# AFPGA.net
KiCad netlist of a schematic drawn in Altium Designer
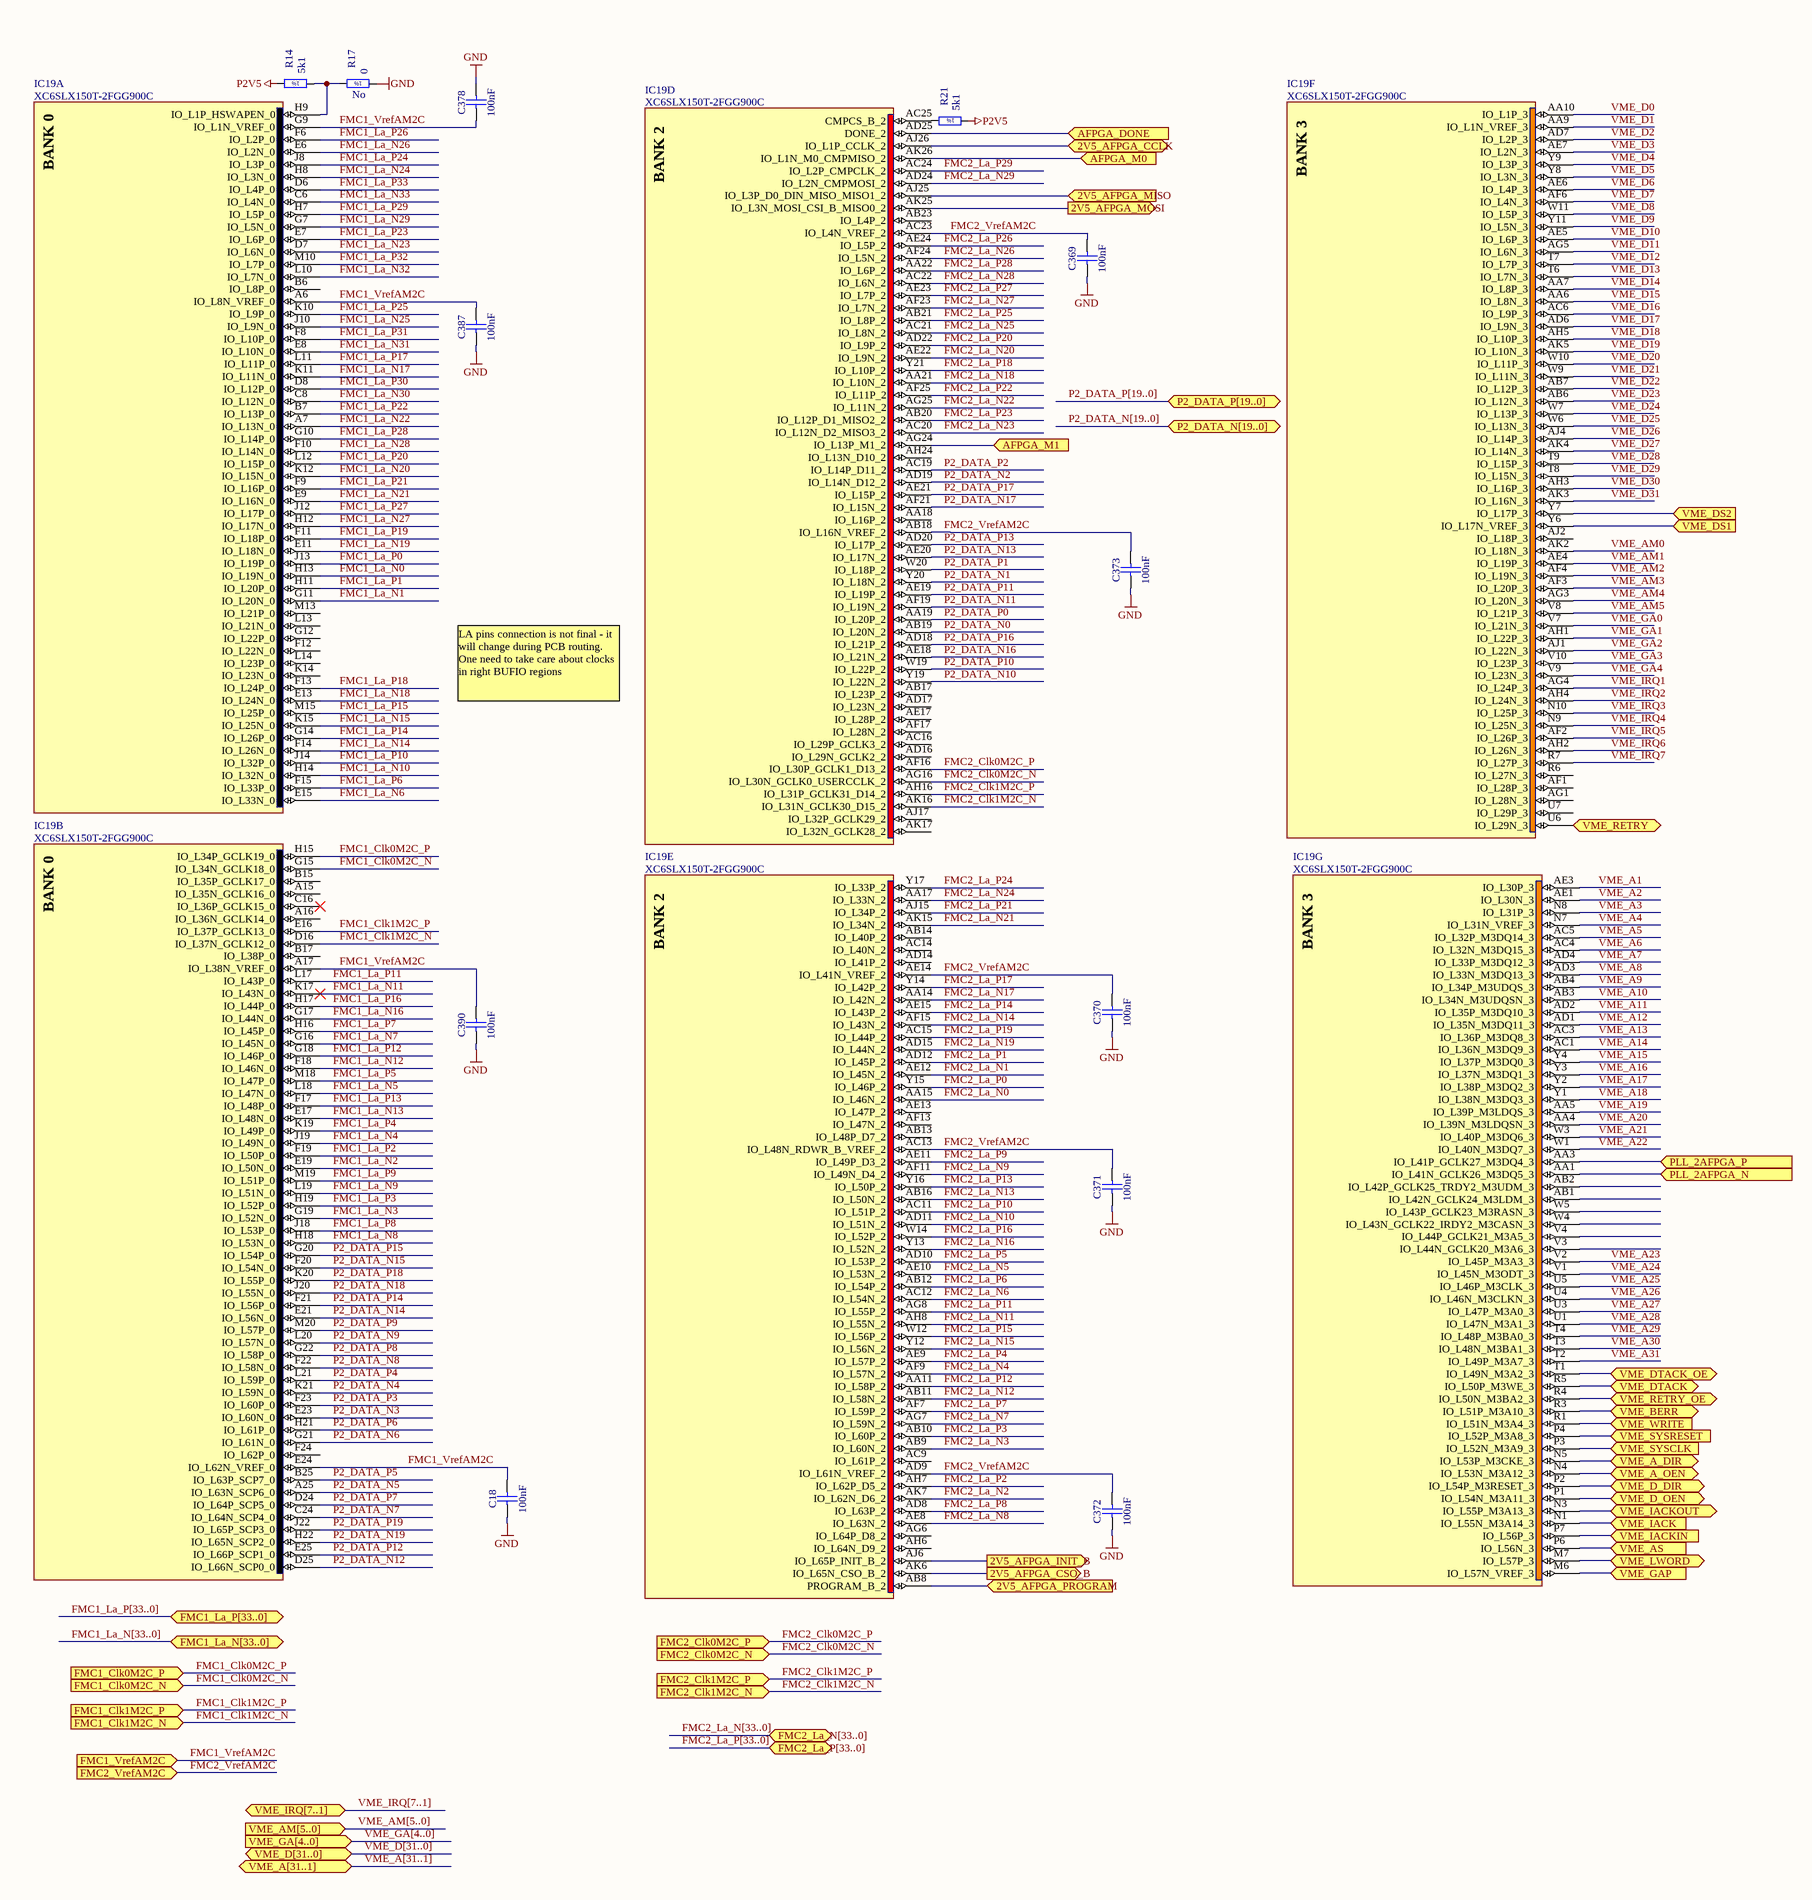
[diagram p0: AFPGA.SchDoc, left]
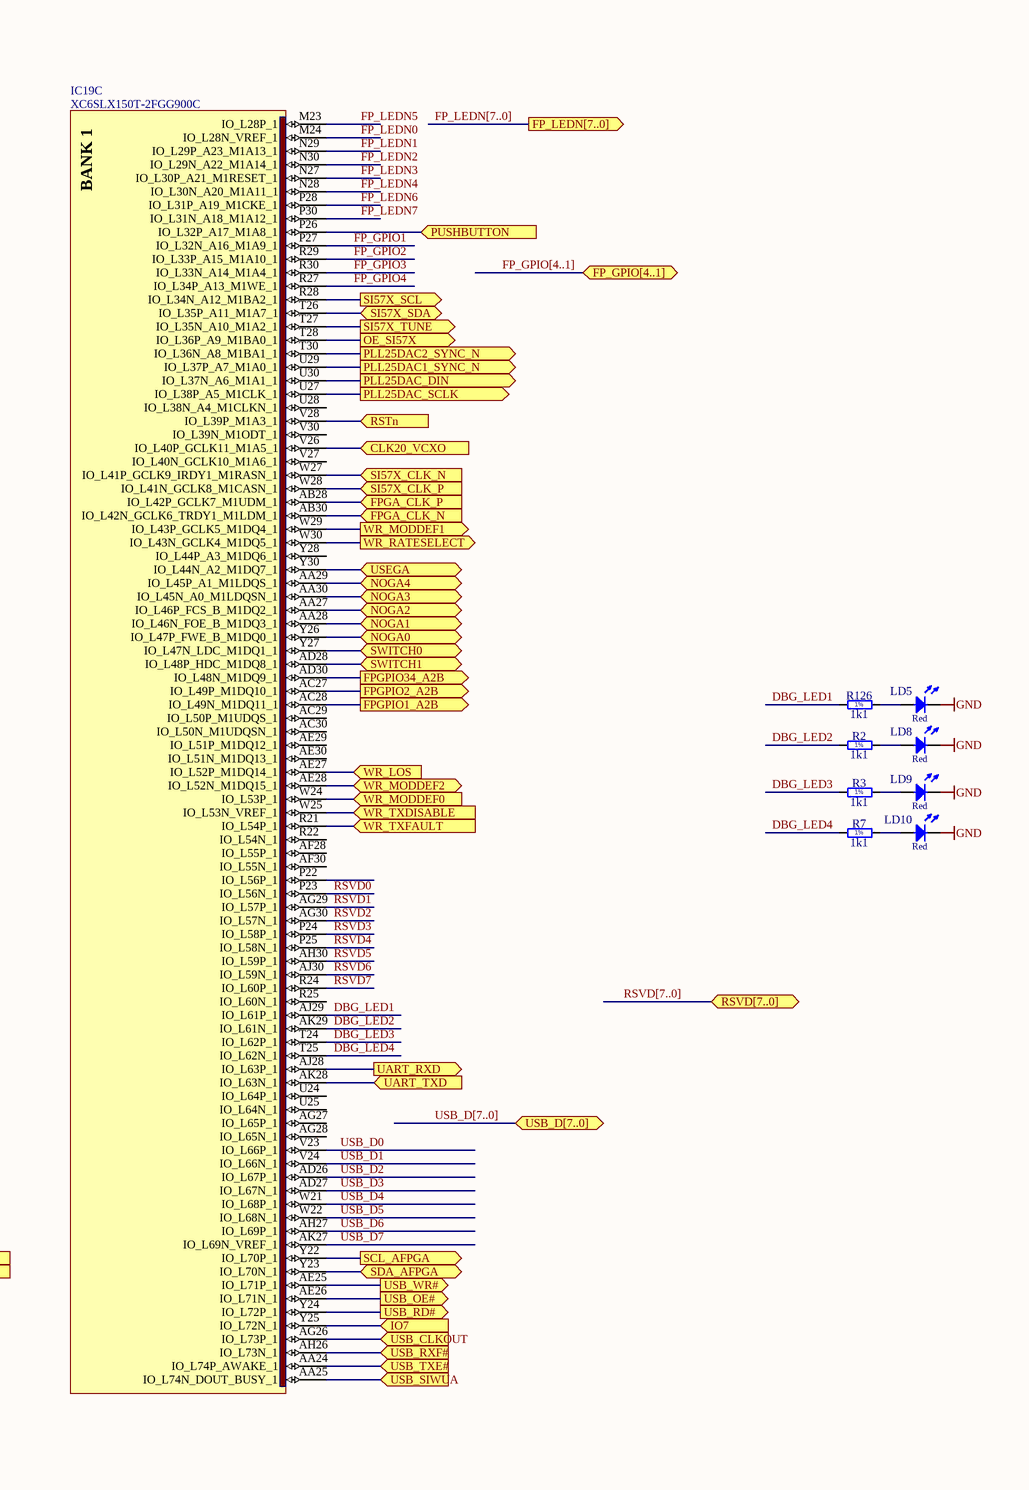
[diagram p1: AFPGA.SchDoc, right]

(export (version "E")
  (design (tool "Eeschema 10.0.6"))
  (components
    (comp (ref "C18")
      (value "100nF")
      (footprint "CAPC1005X55N")
      (description "Non-polarised capacitor")
      (fields
        (field (name "PART NUMBER") "CC0402_100NF_16V_10%_X7R")
        (field (name "VOLTAGE") "16V")
        (field (name "AUTHOR") "CERN DEM JLC")
      )
      (libsource (lib "Capacitors") (part "Capacitor - non polarized"))
    )
    (comp (ref "C369")
      (value "100nF")
      (footprint "CAPC1005X55N")
      (description "Non-polarised capacitor")
      (fields
        (field (name "PART NUMBER") "CC0402_100NF_16V_10%_X7R")
        (field (name "VOLTAGE") "16V")
        (field (name "AUTHOR") "CERN DEM JLC")
      )
      (libsource (lib "Capacitors") (part "Capacitor - non polarized"))
    )
    (comp (ref "C370")
      (value "100nF")
      (footprint "CAPC1005X55N")
      (description "Non-polarised capacitor")
      (fields
        (field (name "PART NUMBER") "CC0402_100NF_16V_10%_X7R")
        (field (name "VOLTAGE") "16V")
        (field (name "AUTHOR") "CERN DEM JLC")
      )
      (libsource (lib "Capacitors") (part "Capacitor - non polarized"))
    )
    (comp (ref "C371")
      (value "100nF")
      (footprint "CAPC1005X55N")
      (description "Non-polarised capacitor")
      (fields
        (field (name "PART NUMBER") "CC0402_100NF_16V_10%_X7R")
        (field (name "VOLTAGE") "16V")
        (field (name "AUTHOR") "CERN DEM JLC")
      )
      (libsource (lib "Capacitors") (part "Capacitor - non polarized"))
    )
    (comp (ref "C372")
      (value "100nF")
      (footprint "CAPC1005X55N")
      (description "Non-polarised capacitor")
      (fields
        (field (name "PART NUMBER") "CC0402_100NF_16V_10%_X7R")
        (field (name "VOLTAGE") "16V")
        (field (name "AUTHOR") "CERN DEM JLC")
      )
      (libsource (lib "Capacitors") (part "Capacitor - non polarized"))
    )
    (comp (ref "C373")
      (value "100nF")
      (footprint "CAPC1005X55N")
      (description "Non-polarised capacitor")
      (fields
        (field (name "PART NUMBER") "CC0402_100NF_16V_10%_X7R")
        (field (name "VOLTAGE") "16V")
        (field (name "AUTHOR") "CERN DEM JLC")
      )
      (libsource (lib "Capacitors") (part "Capacitor - non polarized"))
    )
    (comp (ref "C378")
      (value "100nF")
      (footprint "CAPC1005X55N")
      (description "Non-polarised capacitor")
      (fields
        (field (name "PART NUMBER") "CC0402_100NF_16V_10%_X7R")
        (field (name "VOLTAGE") "16V")
        (field (name "AUTHOR") "CERN DEM JLC")
      )
      (libsource (lib "Capacitors") (part "Capacitor - non polarized"))
    )
    (comp (ref "C387")
      (value "100nF")
      (footprint "CAPC1005X55N")
      (description "Non-polarised capacitor")
      (fields
        (field (name "PART NUMBER") "CC0402_100NF_16V_10%_X7R")
        (field (name "VOLTAGE") "16V")
        (field (name "AUTHOR") "CERN DEM JLC")
      )
      (libsource (lib "Capacitors") (part "Capacitor - non polarized"))
    )
    (comp (ref "C390")
      (value "100nF")
      (footprint "CAPC1005X55N")
      (description "Non-polarised capacitor")
      (fields
        (field (name "PART NUMBER") "CC0402_100NF_16V_10%_X7R")
        (field (name "VOLTAGE") "16V")
        (field (name "AUTHOR") "CERN DEM JLC")
      )
      (libsource (lib "Capacitors") (part "Capacitor - non polarized"))
    )
    (comp (ref "IC19")
      (value "XC6SLX150T-2FGG900C")
      (footprint "BGA900C100P30X30_3100X3100X260")
      (description "SPARTAN-6, FPGA, 900-Ball BGA, Commercial Grade, Pb-Free")
      (fields (field (name "MANUFACTURER") "XILINX") (field (name "AUTHOR") "CERN DEM JLC"))
      (libsource (lib "ICs And Semiconductors") (part "XC6SLX150T-2FGG900C"))
    )
    (comp (ref "LD5")
      (value "Red")
      (footprint "LEDC1608X80N_RED")
      (description "LED Red 1C 2A")
      (fields
        (field (name "PART NUMBER") "LED_ROHM_SML-311UTT86K")
        (field (name "MANUFACTURER") "ROHM")
        (field (name "AUTHOR") "CERN DEM JLC")
      )
      (libsource (lib "ICs And Semiconductors") (part "LED Red 1C 2A"))
    )
    (comp (ref "LD8")
      (value "Red")
      (footprint "LEDC1608X80N_RED")
      (description "LED Red 1C 2A")
      (fields
        (field (name "PART NUMBER") "LED_ROHM_SML-311UTT86K")
        (field (name "MANUFACTURER") "ROHM")
        (field (name "AUTHOR") "CERN DEM JLC")
      )
      (libsource (lib "ICs And Semiconductors") (part "LED Red 1C 2A"))
    )
    (comp (ref "LD9")
      (value "Red")
      (footprint "LEDC1608X80N_RED")
      (description "LED Red 1C 2A")
      (fields
        (field (name "PART NUMBER") "LED_ROHM_SML-311UTT86K")
        (field (name "MANUFACTURER") "ROHM")
        (field (name "AUTHOR") "CERN DEM JLC")
      )
      (libsource (lib "ICs And Semiconductors") (part "LED Red 1C 2A"))
    )
    (comp (ref "LD10")
      (value "Red")
      (footprint "LEDC1608X80N_RED")
      (description "LED Red 1C 2A")
      (fields
        (field (name "PART NUMBER") "LED_ROHM_SML-311UTT86K")
        (field (name "MANUFACTURER") "ROHM")
        (field (name "AUTHOR") "CERN DEM JLC")
      )
      (libsource (lib "ICs And Semiconductors") (part "LED Red 1C 2A"))
    )
    (comp (ref "R2")
      (value "1k1")
      (footprint "RESC1608X55N")
      (description "Resistor - 1%")
      (fields
        (field (name "PART NUMBER") "R0603_1K1_1%_0.1W_100PPM")
        (field (name "POWER") "0.1W")
        (field (name "AUTHOR") "CERN DEM JLC")
      )
      (libsource (lib "Resistors") (part "Resistor - 1%"))
    )
    (comp (ref "R3")
      (value "1k1")
      (footprint "RESC1608X55N")
      (description "Resistor - 1%")
      (fields
        (field (name "PART NUMBER") "R0603_1K1_1%_0.1W_100PPM")
        (field (name "POWER") "0.1W")
        (field (name "AUTHOR") "CERN DEM JLC")
      )
      (libsource (lib "Resistors") (part "Resistor - 1%"))
    )
    (comp (ref "R7")
      (value "1k1")
      (footprint "RESC1608X55N")
      (description "Resistor - 1%")
      (fields
        (field (name "PART NUMBER") "R0603_1K1_1%_0.1W_100PPM")
        (field (name "POWER") "0.1W")
        (field (name "AUTHOR") "CERN DEM JLC")
      )
      (libsource (lib "Resistors") (part "Resistor - 1%"))
    )
    (comp (ref "R14")
      (value "5k1")
      (footprint "RESC1608X55N")
      (description "Resistor - 1%")
      (fields
        (field (name "PART NUMBER") "R0603_5K1_1%_0.1W_100PPM")
        (field (name "POWER") "0.1W")
        (field (name "AUTHOR") "CERN DEM JLC")
      )
      (libsource (lib "Resistors") (part "Resistor - 1%"))
    )
    (comp (ref "R17")
      (value "0")
      (footprint "RESC1608X55N")
      (description "Resistor - 1%")
      (fields
        (field (name "PART NUMBER") "R0603_0R_JUMPER")
        (field (name "MANUFACTURER") "GENERIC")
        (field (name "MOUNTED") "No")
        (field (name "AUTHOR") "CERN DEM JLC")
      )
      (libsource (lib "Resistors") (part "Resistor - 1%"))
    )
    (comp (ref "R21")
      (value "5k1")
      (footprint "RESC1608X55N")
      (description "Resistor - 1%")
      (fields
        (field (name "PART NUMBER") "R0603_5K1_1%_0.1W_100PPM")
        (field (name "POWER") "0.1W")
        (field (name "AUTHOR") "CERN DEM JLC")
      )
      (libsource (lib "Resistors") (part "Resistor - 1%"))
    )
    (comp (ref "R126")
      (value "1k1")
      (footprint "RESC1608X55N")
      (description "Resistor - 1%")
      (fields
        (field (name "PART NUMBER") "R0603_1K1_1%_0.1W_100PPM")
        (field (name "POWER") "0.1W")
        (field (name "AUTHOR") "CERN DEM JLC")
      )
      (libsource (lib "Resistors") (part "Resistor - 1%"))
    )
  )
  (nets
    (net (code "9") (name "/2V5_AFPGA_CCLK") (class "Default")
      (node (ref "IC19") (pin "AJ26") (pinfunction "IO_L1P_CCLK_2_AJ26") (pintype "bidirectional"))
    )
    (net (code "10") (name "/2V5_AFPGA_CSO_B") (class "Default")
      (node (ref "IC19") (pin "AK6") (pinfunction "IO_L65N_CSO_B_2_AK6") (pintype "bidirectional"))
    )
    (net (code "11") (name "/2V5_AFPGA_INIT_B") (class "Default")
      (node (ref "IC19") (pin "AJ6") (pinfunction "IO_L65P_INIT_B_2_AJ6") (pintype "bidirectional"))
    )
    (net (code "12") (name "/2V5_AFPGA_MISO") (class "Default")
      (node (ref "IC19") (pin "AJ25") (pinfunction "IO_L3P_D0_DIN_MISO_MISO1_2_AJ25") (pintype "bidirectional"))
    )
    (net (code "13") (name "/2V5_AFPGA_MOSI") (class "Default")
      (node (ref "IC19") (pin "AK25") (pinfunction "IO_L3N_MOSI_CSI_B_MISO0_2_AK25") (pintype "bidirectional"))
    )
    (net (code "14") (name "/2V5_AFPGA_PROGRAM") (class "Default")
      (node (ref "IC19") (pin "AB8") (pinfunction "PROGRAM_B_2_AB8") (pintype "bidirectional"))
    )
    (net (code "15") (name "/AFPGA_DONE") (class "Default")
      (node (ref "IC19") (pin "AD25") (pinfunction "DONE_2_AD25") (pintype "bidirectional"))
    )
    (net (code "16") (name "/AFPGA_M0") (class "Default")
      (node (ref "IC19") (pin "AK26") (pinfunction "IO_L1N_M0_CMPMISO_2_AK26") (pintype "bidirectional"))
    )
    (net (code "17") (name "/AFPGA_M1") (class "Default")
      (node (ref "IC19") (pin "AG24") (pinfunction "IO_L13P_M1_2_AG24") (pintype "bidirectional"))
    )
    (net (code "18") (name "/CLK20_VCXO") (class "Default")
      (node (ref "IC19") (pin "V26") (pinfunction "IO_L40P_GCLK11_M1A5_1_V26") (pintype "bidirectional"))
    )
    (net (code "19") (name "/DBG_LED1") (class "Default")
      (node (ref "IC19") (pin "AJ29") (pinfunction "IO_L61P_1_AJ29") (pintype "bidirectional"))
      (node (ref "R126") (pin "1") (pinfunction "1_1") (pintype "passive"))
    )
    (net (code "20") (name "/DBG_LED2") (class "Default")
      (node (ref "IC19") (pin "AK29") (pinfunction "IO_L61N_1_AK29") (pintype "bidirectional"))
      (node (ref "R2") (pin "1") (pinfunction "1_1") (pintype "passive"))
    )
    (net (code "21") (name "/DBG_LED3") (class "Default")
      (node (ref "IC19") (pin "T24") (pinfunction "IO_L62P_1_T24") (pintype "bidirectional"))
      (node (ref "R3") (pin "1") (pinfunction "1_1") (pintype "passive"))
    )
    (net (code "22") (name "/DBG_LED4") (class "Default")
      (node (ref "IC19") (pin "T25") (pinfunction "IO_L62N_1_T25") (pintype "bidirectional"))
      (node (ref "R7") (pin "1") (pinfunction "1_1") (pintype "passive"))
    )
    (net (code "23") (name "/FMC1_Clk0M2C_N") (class "Default")
      (node (ref "IC19") (pin "G15") (pinfunction "IO_L34N_GCLK18_0_G15") (pintype "bidirectional"))
    )
    (net (code "24") (name "/FMC1_Clk0M2C_P") (class "Default")
      (node (ref "IC19") (pin "H15") (pinfunction "IO_L34P_GCLK19_0_H15") (pintype "bidirectional"))
    )
    (net (code "25") (name "/FMC1_Clk1M2C_N") (class "Default")
      (node (ref "IC19") (pin "D16") (pinfunction "IO_L37N_GCLK12_0_D16") (pintype "bidirectional"))
    )
    (net (code "26") (name "/FMC1_Clk1M2C_P") (class "Default")
      (node (ref "IC19") (pin "E16") (pinfunction "IO_L37P_GCLK13_0_E16") (pintype "bidirectional"))
    )
    (net (code "27") (name "/FMC1_La_N0") (class "Default")
      (node (ref "IC19") (pin "H13") (pinfunction "IO_L19N_0_H13") (pintype "bidirectional"))
    )
    (net (code "28") (name "/FMC1_La_N1") (class "Default")
      (node (ref "IC19") (pin "G11") (pinfunction "IO_L20N_0_G11") (pintype "bidirectional"))
    )
    (net (code "29") (name "/FMC1_La_N2") (class "Default")
      (node (ref "IC19") (pin "E19") (pinfunction "IO_L50N_0_E19") (pintype "bidirectional"))
    )
    (net (code "30") (name "/FMC1_La_N3") (class "Default")
      (node (ref "IC19") (pin "G19") (pinfunction "IO_L52N_0_G19") (pintype "bidirectional"))
    )
    (net (code "31") (name "/FMC1_La_N4") (class "Default")
      (node (ref "IC19") (pin "J19") (pinfunction "IO_L49N_0_J19") (pintype "bidirectional"))
    )
    (net (code "32") (name "/FMC1_La_N5") (class "Default")
      (node (ref "IC19") (pin "L18") (pinfunction "IO_L47N_0_L18") (pintype "bidirectional"))
    )
    (net (code "33") (name "/FMC1_La_N6") (class "Default")
      (node (ref "IC19") (pin "E15") (pinfunction "IO_L33N_0_E15") (pintype "bidirectional"))
    )
    (net (code "34") (name "/FMC1_La_N7") (class "Default")
      (node (ref "IC19") (pin "G16") (pinfunction "IO_L45N_0_G16") (pintype "bidirectional"))
    )
    (net (code "35") (name "/FMC1_La_N8") (class "Default")
      (node (ref "IC19") (pin "H18") (pinfunction "IO_L53N_0_H18") (pintype "bidirectional"))
    )
    (net (code "36") (name "/FMC1_La_N9") (class "Default")
      (node (ref "IC19") (pin "L19") (pinfunction "IO_L51N_0_L19") (pintype "bidirectional"))
    )
    (net (code "37") (name "/FMC1_La_N10") (class "Default")
      (node (ref "IC19") (pin "H14") (pinfunction "IO_L32N_0_H14") (pintype "bidirectional"))
    )
    (net (code "38") (name "/FMC1_La_N11") (class "Default")
      (node (ref "IC19") (pin "K17") (pinfunction "IO_L43N_0_K17") (pintype "bidirectional+no_connect"))
    )
    (net (code "39") (name "/FMC1_La_N12") (class "Default")
      (node (ref "IC19") (pin "F18") (pinfunction "IO_L46N_0_F18") (pintype "bidirectional"))
    )
    (net (code "40") (name "/FMC1_La_N13") (class "Default")
      (node (ref "IC19") (pin "E17") (pinfunction "IO_L48N_0_E17") (pintype "bidirectional"))
    )
    (net (code "41") (name "/FMC1_La_N14") (class "Default")
      (node (ref "IC19") (pin "F14") (pinfunction "IO_L26N_0_F14") (pintype "bidirectional"))
    )
    (net (code "42") (name "/FMC1_La_N15") (class "Default")
      (node (ref "IC19") (pin "K15") (pinfunction "IO_L25N_0_K15") (pintype "bidirectional"))
    )
    (net (code "43") (name "/FMC1_La_N16") (class "Default")
      (node (ref "IC19") (pin "G17") (pinfunction "IO_L44N_0_G17") (pintype "bidirectional"))
    )
    (net (code "44") (name "/FMC1_La_N17") (class "Default")
      (node (ref "IC19") (pin "K11") (pinfunction "IO_L11N_0_K11") (pintype "bidirectional"))
    )
    (net (code "45") (name "/FMC1_La_N18") (class "Default")
      (node (ref "IC19") (pin "E13") (pinfunction "IO_L24N_0_E13") (pintype "bidirectional"))
    )
    (net (code "46") (name "/FMC1_La_N19") (class "Default")
      (node (ref "IC19") (pin "E11") (pinfunction "IO_L18N_0_E11") (pintype "bidirectional"))
    )
    (net (code "47") (name "/FMC1_La_N20") (class "Default")
      (node (ref "IC19") (pin "K12") (pinfunction "IO_L15N_0_K12") (pintype "bidirectional"))
    )
    (net (code "48") (name "/FMC1_La_N21") (class "Default")
      (node (ref "IC19") (pin "E9") (pinfunction "IO_L16N_0_E9") (pintype "bidirectional"))
    )
    (net (code "49") (name "/FMC1_La_N22") (class "Default")
      (node (ref "IC19") (pin "A7") (pinfunction "IO_L13N_0_A7") (pintype "bidirectional"))
    )
    (net (code "50") (name "/FMC1_La_N23") (class "Default")
      (node (ref "IC19") (pin "D7") (pinfunction "IO_L6N_0_D7") (pintype "bidirectional"))
    )
    (net (code "51") (name "/FMC1_La_N24") (class "Default")
      (node (ref "IC19") (pin "H8") (pinfunction "IO_L3N_0_H8") (pintype "bidirectional"))
    )
    (net (code "52") (name "/FMC1_La_N25") (class "Default")
      (node (ref "IC19") (pin "J10") (pinfunction "IO_L9N_0_J10") (pintype "bidirectional"))
    )
    (net (code "53") (name "/FMC1_La_N26") (class "Default")
      (node (ref "IC19") (pin "E6") (pinfunction "IO_L2N_0_E6") (pintype "bidirectional"))
    )
    (net (code "54") (name "/FMC1_La_N27") (class "Default")
      (node (ref "IC19") (pin "H12") (pinfunction "IO_L17N_0_H12") (pintype "bidirectional"))
    )
    (net (code "55") (name "/FMC1_La_N28") (class "Default")
      (node (ref "IC19") (pin "F10") (pinfunction "IO_L14N_0_F10") (pintype "bidirectional"))
    )
    (net (code "56") (name "/FMC1_La_N29") (class "Default")
      (node (ref "IC19") (pin "G7") (pinfunction "IO_L5N_0_G7") (pintype "bidirectional"))
    )
    (net (code "57") (name "/FMC1_La_N30") (class "Default")
      (node (ref "IC19") (pin "C8") (pinfunction "IO_L12N_0_C8") (pintype "bidirectional"))
    )
    (net (code "58") (name "/FMC1_La_N31") (class "Default")
      (node (ref "IC19") (pin "E8") (pinfunction "IO_L10N_0_E8") (pintype "bidirectional"))
    )
    (net (code "59") (name "/FMC1_La_N32") (class "Default")
      (node (ref "IC19") (pin "L10") (pinfunction "IO_L7N_0_L10") (pintype "bidirectional"))
    )
    (net (code "60") (name "/FMC1_La_N33") (class "Default")
      (node (ref "IC19") (pin "C6") (pinfunction "IO_L4N_0_C6") (pintype "bidirectional"))
    )
    (net (code "62") (name "/FMC1_La_P0") (class "Default")
      (node (ref "IC19") (pin "J13") (pinfunction "IO_L19P_0_J13") (pintype "bidirectional"))
    )
    (net (code "63") (name "/FMC1_La_P1") (class "Default")
      (node (ref "IC19") (pin "H11") (pinfunction "IO_L20P_0_H11") (pintype "bidirectional"))
    )
    (net (code "64") (name "/FMC1_La_P2") (class "Default")
      (node (ref "IC19") (pin "F19") (pinfunction "IO_L50P_0_F19") (pintype "bidirectional"))
    )
    (net (code "65") (name "/FMC1_La_P3") (class "Default")
      (node (ref "IC19") (pin "H19") (pinfunction "IO_L52P_0_H19") (pintype "bidirectional"))
    )
    (net (code "66") (name "/FMC1_La_P4") (class "Default")
      (node (ref "IC19") (pin "K19") (pinfunction "IO_L49P_0_K19") (pintype "bidirectional"))
    )
    (net (code "67") (name "/FMC1_La_P5") (class "Default")
      (node (ref "IC19") (pin "M18") (pinfunction "IO_L47P_0_M18") (pintype "bidirectional"))
    )
    (net (code "68") (name "/FMC1_La_P6") (class "Default")
      (node (ref "IC19") (pin "F15") (pinfunction "IO_L33P_0_F15") (pintype "bidirectional"))
    )
    (net (code "69") (name "/FMC1_La_P7") (class "Default")
      (node (ref "IC19") (pin "H16") (pinfunction "IO_L45P_0_H16") (pintype "bidirectional"))
    )
    (net (code "70") (name "/FMC1_La_P8") (class "Default")
      (node (ref "IC19") (pin "J18") (pinfunction "IO_L53P_0_J18") (pintype "bidirectional"))
    )
    (net (code "71") (name "/FMC1_La_P9") (class "Default")
      (node (ref "IC19") (pin "M19") (pinfunction "IO_L51P_0_M19") (pintype "bidirectional"))
    )
    (net (code "72") (name "/FMC1_La_P10") (class "Default")
      (node (ref "IC19") (pin "J14") (pinfunction "IO_L32P_0_J14") (pintype "bidirectional"))
    )
    (net (code "73") (name "/FMC1_La_P11") (class "Default")
      (node (ref "IC19") (pin "L17") (pinfunction "IO_L43P_0_L17") (pintype "bidirectional"))
    )
    (net (code "74") (name "/FMC1_La_P12") (class "Default")
      (node (ref "IC19") (pin "G18") (pinfunction "IO_L46P_0_G18") (pintype "bidirectional"))
    )
    (net (code "75") (name "/FMC1_La_P13") (class "Default")
      (node (ref "IC19") (pin "F17") (pinfunction "IO_L48P_0_F17") (pintype "bidirectional"))
    )
    (net (code "76") (name "/FMC1_La_P14") (class "Default")
      (node (ref "IC19") (pin "G14") (pinfunction "IO_L26P_0_G14") (pintype "bidirectional"))
    )
    (net (code "77") (name "/FMC1_La_P15") (class "Default")
      (node (ref "IC19") (pin "M15") (pinfunction "IO_L25P_0_M15") (pintype "bidirectional"))
    )
    (net (code "78") (name "/FMC1_La_P16") (class "Default")
      (node (ref "IC19") (pin "H17") (pinfunction "IO_L44P_0_H17") (pintype "bidirectional"))
    )
    (net (code "79") (name "/FMC1_La_P17") (class "Default")
      (node (ref "IC19") (pin "L11") (pinfunction "IO_L11P_0_L11") (pintype "bidirectional"))
    )
    (net (code "80") (name "/FMC1_La_P18") (class "Default")
      (node (ref "IC19") (pin "F13") (pinfunction "IO_L24P_0_F13") (pintype "bidirectional"))
    )
    (net (code "81") (name "/FMC1_La_P19") (class "Default")
      (node (ref "IC19") (pin "F11") (pinfunction "IO_L18P_0_F11") (pintype "bidirectional"))
    )
    (net (code "82") (name "/FMC1_La_P20") (class "Default")
      (node (ref "IC19") (pin "L12") (pinfunction "IO_L15P_0_L12") (pintype "bidirectional"))
    )
    (net (code "83") (name "/FMC1_La_P21") (class "Default")
      (node (ref "IC19") (pin "F9") (pinfunction "IO_L16P_0_F9") (pintype "bidirectional"))
    )
    (net (code "84") (name "/FMC1_La_P22") (class "Default")
      (node (ref "IC19") (pin "B7") (pinfunction "IO_L13P_0_B7") (pintype "bidirectional"))
    )
    (net (code "85") (name "/FMC1_La_P23") (class "Default")
      (node (ref "IC19") (pin "E7") (pinfunction "IO_L6P_0_E7") (pintype "bidirectional"))
    )
    (net (code "86") (name "/FMC1_La_P24") (class "Default")
      (node (ref "IC19") (pin "J8") (pinfunction "IO_L3P_0_J8") (pintype "bidirectional"))
    )
    (net (code "87") (name "/FMC1_La_P25") (class "Default")
      (node (ref "IC19") (pin "K10") (pinfunction "IO_L9P_0_K10") (pintype "bidirectional"))
    )
    (net (code "88") (name "/FMC1_La_P26") (class "Default")
      (node (ref "IC19") (pin "F6") (pinfunction "IO_L2P_0_F6") (pintype "bidirectional"))
    )
    (net (code "89") (name "/FMC1_La_P27") (class "Default")
      (node (ref "IC19") (pin "J12") (pinfunction "IO_L17P_0_J12") (pintype "bidirectional"))
    )
    (net (code "90") (name "/FMC1_La_P28") (class "Default")
      (node (ref "IC19") (pin "G10") (pinfunction "IO_L14P_0_G10") (pintype "bidirectional"))
    )
    (net (code "91") (name "/FMC1_La_P29") (class "Default")
      (node (ref "IC19") (pin "H7") (pinfunction "IO_L5P_0_H7") (pintype "bidirectional"))
    )
    (net (code "92") (name "/FMC1_La_P30") (class "Default")
      (node (ref "IC19") (pin "D8") (pinfunction "IO_L12P_0_D8") (pintype "bidirectional"))
    )
    (net (code "93") (name "/FMC1_La_P31") (class "Default")
      (node (ref "IC19") (pin "F8") (pinfunction "IO_L10P_0_F8") (pintype "bidirectional"))
    )
    (net (code "94") (name "/FMC1_La_P32") (class "Default")
      (node (ref "IC19") (pin "M10") (pinfunction "IO_L7P_0_M10") (pintype "bidirectional"))
    )
    (net (code "95") (name "/FMC1_La_P33") (class "Default")
      (node (ref "IC19") (pin "D6") (pinfunction "IO_L4P_0_D6") (pintype "bidirectional"))
    )
    (net (code "97") (name "/FMC1_VrefAM2C") (class "Default")
      (node (ref "C18") (pin "2") (pinfunction "2_2") (pintype "passive"))
      (node (ref "C378") (pin "1") (pinfunction "1_1") (pintype "passive"))
      (node (ref "C387") (pin "2") (pinfunction "2_2") (pintype "passive"))
      (node (ref "C390") (pin "2") (pinfunction "2_2") (pintype "passive"))
      (node (ref "IC19") (pin "A17") (pinfunction "IO_L38N_VREF_0_A17") (pintype "bidirectional"))
      (node (ref "IC19") (pin "A6") (pinfunction "IO_L8N_VREF_0_A6") (pintype "bidirectional"))
      (node (ref "IC19") (pin "E24") (pinfunction "IO_L62N_VREF_0_E24") (pintype "bidirectional"))
      (node (ref "IC19") (pin "G9") (pinfunction "IO_L1N_VREF_0_G9") (pintype "bidirectional"))
    )
    (net (code "98") (name "/FMC2_Clk0M2C_N") (class "Default")
      (node (ref "IC19") (pin "AG16") (pinfunction "IO_L30N_GCLK0_USERCCLK_2_AG16") (pintype "bidirectional"))
    )
    (net (code "99") (name "/FMC2_Clk0M2C_P") (class "Default")
      (node (ref "IC19") (pin "AF16") (pinfunction "IO_L30P_GCLK1_D13_2_AF16") (pintype "bidirectional"))
    )
    (net (code "100") (name "/FMC2_Clk1M2C_N") (class "Default")
      (node (ref "IC19") (pin "AK16") (pinfunction "IO_L31N_GCLK30_D15_2_AK16") (pintype "bidirectional"))
    )
    (net (code "101") (name "/FMC2_Clk1M2C_P") (class "Default")
      (node (ref "IC19") (pin "AH16") (pinfunction "IO_L31P_GCLK31_D14_2_AH16") (pintype "bidirectional"))
    )
    (net (code "102") (name "/FMC2_La_N0") (class "Default")
      (node (ref "IC19") (pin "AA15") (pinfunction "IO_L46N_2_AA15") (pintype "bidirectional"))
    )
    (net (code "103") (name "/FMC2_La_N1") (class "Default")
      (node (ref "IC19") (pin "AE12") (pinfunction "IO_L45N_2_AE12") (pintype "bidirectional"))
    )
    (net (code "104") (name "/FMC2_La_N2") (class "Default")
      (node (ref "IC19") (pin "AK7") (pinfunction "IO_L62N_D6_2_AK7") (pintype "bidirectional"))
    )
    (net (code "105") (name "/FMC2_La_N3") (class "Default")
      (node (ref "IC19") (pin "AB9") (pinfunction "IO_L60N_2_AB9") (pintype "bidirectional"))
    )
    (net (code "106") (name "/FMC2_La_N4") (class "Default")
      (node (ref "IC19") (pin "AF9") (pinfunction "IO_L57N_2_AF9") (pintype "bidirectional"))
    )
    (net (code "107") (name "/FMC2_La_N5") (class "Default")
      (node (ref "IC19") (pin "AE10") (pinfunction "IO_L53N_2_AE10") (pintype "bidirectional"))
    )
    (net (code "108") (name "/FMC2_La_N6") (class "Default")
      (node (ref "IC19") (pin "AC12") (pinfunction "IO_L54N_2_AC12") (pintype "bidirectional"))
    )
    (net (code "109") (name "/FMC2_La_N7") (class "Default")
      (node (ref "IC19") (pin "AG7") (pinfunction "IO_L59N_2_AG7") (pintype "bidirectional"))
    )
    (net (code "110") (name "/FMC2_La_N8") (class "Default")
      (node (ref "IC19") (pin "AE8") (pinfunction "IO_L63N_2_AE8") (pintype "bidirectional"))
    )
    (net (code "111") (name "/FMC2_La_N9") (class "Default")
      (node (ref "IC19") (pin "AF11") (pinfunction "IO_L49N_D4_2_AF11") (pintype "bidirectional"))
    )
    (net (code "112") (name "/FMC2_La_N10") (class "Default")
      (node (ref "IC19") (pin "AD11") (pinfunction "IO_L51N_2_AD11") (pintype "bidirectional"))
    )
    (net (code "113") (name "/FMC2_La_N11") (class "Default")
      (node (ref "IC19") (pin "AH8") (pinfunction "IO_L55N_2_AH8") (pintype "bidirectional"))
    )
    (net (code "114") (name "/FMC2_La_N12") (class "Default")
      (node (ref "IC19") (pin "AB11") (pinfunction "IO_L58N_2_AB11") (pintype "bidirectional"))
    )
    (net (code "115") (name "/FMC2_La_N13") (class "Default")
      (node (ref "IC19") (pin "AB16") (pinfunction "IO_L50N_2_AB16") (pintype "bidirectional"))
    )
    (net (code "116") (name "/FMC2_La_N14") (class "Default")
      (node (ref "IC19") (pin "AF15") (pinfunction "IO_L43N_2_AF15") (pintype "bidirectional"))
    )
    (net (code "117") (name "/FMC2_La_N15") (class "Default")
      (node (ref "IC19") (pin "Y12") (pinfunction "IO_L56N_2_Y12") (pintype "bidirectional"))
    )
    (net (code "118") (name "/FMC2_La_N16") (class "Default")
      (node (ref "IC19") (pin "Y13") (pinfunction "IO_L52N_2_Y13") (pintype "bidirectional"))
    )
    (net (code "119") (name "/FMC2_La_N17") (class "Default")
      (node (ref "IC19") (pin "AA14") (pinfunction "IO_L42N_2_AA14") (pintype "bidirectional"))
    )
    (net (code "120") (name "/FMC2_La_N18") (class "Default")
      (node (ref "IC19") (pin "AA21") (pinfunction "IO_L10N_2_AA21") (pintype "bidirectional"))
    )
    (net (code "121") (name "/FMC2_La_N19") (class "Default")
      (node (ref "IC19") (pin "AD15") (pinfunction "IO_L44N_2_AD15") (pintype "bidirectional"))
    )
    (net (code "122") (name "/FMC2_La_N20") (class "Default")
      (node (ref "IC19") (pin "AE22") (pinfunction "IO_L9N_2_AE22") (pintype "bidirectional"))
    )
    (net (code "123") (name "/FMC2_La_N21") (class "Default")
      (node (ref "IC19") (pin "AK15") (pinfunction "IO_L34N_2_AK15") (pintype "bidirectional"))
    )
    (net (code "124") (name "/FMC2_La_N22") (class "Default")
      (node (ref "IC19") (pin "AG25") (pinfunction "IO_L11N_2_AG25") (pintype "bidirectional"))
    )
    (net (code "125") (name "/FMC2_La_N23") (class "Default")
      (node (ref "IC19") (pin "AC20") (pinfunction "IO_L12N_D2_MISO3_2_AC20") (pintype "bidirectional"))
    )
    (net (code "126") (name "/FMC2_La_N24") (class "Default")
      (node (ref "IC19") (pin "AA17") (pinfunction "IO_L33N_2_AA17") (pintype "bidirectional"))
    )
    (net (code "127") (name "/FMC2_La_N25") (class "Default")
      (node (ref "IC19") (pin "AC21") (pinfunction "IO_L8N_2_AC21") (pintype "bidirectional"))
    )
    (net (code "128") (name "/FMC2_La_N26") (class "Default")
      (node (ref "IC19") (pin "AF24") (pinfunction "IO_L5N_2_AF24") (pintype "bidirectional"))
    )
    (net (code "129") (name "/FMC2_La_N27") (class "Default")
      (node (ref "IC19") (pin "AF23") (pinfunction "IO_L7N_2_AF23") (pintype "bidirectional"))
    )
    (net (code "130") (name "/FMC2_La_N28") (class "Default")
      (node (ref "IC19") (pin "AC22") (pinfunction "IO_L6N_2_AC22") (pintype "bidirectional"))
    )
    (net (code "131") (name "/FMC2_La_N29") (class "Default")
      (node (ref "IC19") (pin "AD24") (pinfunction "IO_L2N_CMPMOSI_2_AD24") (pintype "bidirectional"))
    )
    (net (code "133") (name "/FMC2_La_P0") (class "Default")
      (node (ref "IC19") (pin "Y15") (pinfunction "IO_L46P_2_Y15") (pintype "bidirectional"))
    )
    (net (code "134") (name "/FMC2_La_P1") (class "Default")
      (node (ref "IC19") (pin "AD12") (pinfunction "IO_L45P_2_AD12") (pintype "bidirectional"))
    )
    (net (code "135") (name "/FMC2_La_P2") (class "Default")
      (node (ref "IC19") (pin "AH7") (pinfunction "IO_L62P_D5_2_AH7") (pintype "bidirectional"))
    )
    (net (code "136") (name "/FMC2_La_P3") (class "Default")
      (node (ref "IC19") (pin "AB10") (pinfunction "IO_L60P_2_AB10") (pintype "bidirectional"))
    )
    (net (code "137") (name "/FMC2_La_P4") (class "Default")
      (node (ref "IC19") (pin "AE9") (pinfunction "IO_L57P_2_AE9") (pintype "bidirectional"))
    )
    (net (code "138") (name "/FMC2_La_P5") (class "Default")
      (node (ref "IC19") (pin "AD10") (pinfunction "IO_L53P_2_AD10") (pintype "bidirectional"))
    )
    (net (code "139") (name "/FMC2_La_P6") (class "Default")
      (node (ref "IC19") (pin "AB12") (pinfunction "IO_L54P_2_AB12") (pintype "bidirectional"))
    )
    (net (code "140") (name "/FMC2_La_P7") (class "Default")
      (node (ref "IC19") (pin "AF7") (pinfunction "IO_L59P_2_AF7") (pintype "bidirectional"))
    )
    (net (code "141") (name "/FMC2_La_P8") (class "Default")
      (node (ref "IC19") (pin "AD8") (pinfunction "IO_L63P_2_AD8") (pintype "bidirectional"))
    )
    (net (code "142") (name "/FMC2_La_P9") (class "Default")
      (node (ref "IC19") (pin "AE11") (pinfunction "IO_L49P_D3_2_AE11") (pintype "bidirectional"))
    )
    (net (code "143") (name "/FMC2_La_P10") (class "Default")
      (node (ref "IC19") (pin "AC11") (pinfunction "IO_L51P_2_AC11") (pintype "bidirectional"))
    )
    (net (code "144") (name "/FMC2_La_P11") (class "Default")
      (node (ref "IC19") (pin "AG8") (pinfunction "IO_L55P_2_AG8") (pintype "bidirectional"))
    )
    (net (code "145") (name "/FMC2_La_P12") (class "Default")
      (node (ref "IC19") (pin "AA11") (pinfunction "IO_L58P_2_AA11") (pintype "bidirectional"))
    )
    (net (code "146") (name "/FMC2_La_P13") (class "Default")
      (node (ref "IC19") (pin "Y16") (pinfunction "IO_L50P_2_Y16") (pintype "bidirectional"))
    )
    (net (code "147") (name "/FMC2_La_P14") (class "Default")
      (node (ref "IC19") (pin "AE15") (pinfunction "IO_L43P_2_AE15") (pintype "bidirectional"))
    )
    (net (code "148") (name "/FMC2_La_P15") (class "Default")
      (node (ref "IC19") (pin "W12") (pinfunction "IO_L56P_2_W12") (pintype "bidirectional"))
    )
    (net (code "149") (name "/FMC2_La_P16") (class "Default")
      (node (ref "IC19") (pin "W14") (pinfunction "IO_L52P_2_W14") (pintype "bidirectional"))
    )
    (net (code "150") (name "/FMC2_La_P17") (class "Default")
      (node (ref "IC19") (pin "Y14") (pinfunction "IO_L42P_2_Y14") (pintype "bidirectional"))
    )
    (net (code "151") (name "/FMC2_La_P18") (class "Default")
      (node (ref "IC19") (pin "Y21") (pinfunction "IO_L10P_2_Y21") (pintype "bidirectional"))
    )
    (net (code "152") (name "/FMC2_La_P19") (class "Default")
      (node (ref "IC19") (pin "AC15") (pinfunction "IO_L44P_2_AC15") (pintype "bidirectional"))
    )
    (net (code "153") (name "/FMC2_La_P20") (class "Default")
      (node (ref "IC19") (pin "AD22") (pinfunction "IO_L9P_2_AD22") (pintype "bidirectional"))
    )
    (net (code "154") (name "/FMC2_La_P21") (class "Default")
      (node (ref "IC19") (pin "AJ15") (pinfunction "IO_L34P_2_AJ15") (pintype "bidirectional"))
    )
    (net (code "155") (name "/FMC2_La_P22") (class "Default")
      (node (ref "IC19") (pin "AF25") (pinfunction "IO_L11P_2_AF25") (pintype "bidirectional"))
    )
    (net (code "156") (name "/FMC2_La_P23") (class "Default")
      (node (ref "IC19") (pin "AB20") (pinfunction "IO_L12P_D1_MISO2_2_AB20") (pintype "bidirectional"))
    )
    (net (code "157") (name "/FMC2_La_P24") (class "Default")
      (node (ref "IC19") (pin "Y17") (pinfunction "IO_L33P_2_Y17") (pintype "bidirectional"))
    )
    (net (code "158") (name "/FMC2_La_P25") (class "Default")
      (node (ref "IC19") (pin "AB21") (pinfunction "IO_L8P_2_AB21") (pintype "bidirectional"))
    )
    (net (code "159") (name "/FMC2_La_P26") (class "Default")
      (node (ref "IC19") (pin "AE24") (pinfunction "IO_L5P_2_AE24") (pintype "bidirectional"))
    )
    (net (code "160") (name "/FMC2_La_P27") (class "Default")
      (node (ref "IC19") (pin "AE23") (pinfunction "IO_L7P_2_AE23") (pintype "bidirectional"))
    )
    (net (code "161") (name "/FMC2_La_P28") (class "Default")
      (node (ref "IC19") (pin "AA22") (pinfunction "IO_L6P_2_AA22") (pintype "bidirectional"))
    )
    (net (code "162") (name "/FMC2_La_P29") (class "Default")
      (node (ref "IC19") (pin "AC24") (pinfunction "IO_L2P_CMPCLK_2_AC24") (pintype "bidirectional"))
    )
    (net (code "164") (name "/FMC2_VrefAM2C") (class "Default")
      (node (ref "C369") (pin "2") (pinfunction "2_2") (pintype "passive"))
      (node (ref "C370") (pin "2") (pinfunction "2_2") (pintype "passive"))
      (node (ref "C371") (pin "2") (pinfunction "2_2") (pintype "passive"))
      (node (ref "C372") (pin "2") (pinfunction "2_2") (pintype "passive"))
      (node (ref "C373") (pin "2") (pinfunction "2_2") (pintype "passive"))
      (node (ref "IC19") (pin "AB18") (pinfunction "IO_L16N_VREF_2_AB18") (pintype "bidirectional"))
      (node (ref "IC19") (pin "AC13") (pinfunction "IO_L48N_RDWR_B_VREF_2_AC13") (pintype "bidirectional"))
      (node (ref "IC19") (pin "AC23") (pinfunction "IO_L4N_VREF_2_AC23") (pintype "bidirectional"))
      (node (ref "IC19") (pin "AD9") (pinfunction "IO_L61N_VREF_2_AD9") (pintype "bidirectional"))
      (node (ref "IC19") (pin "AE14") (pinfunction "IO_L41N_VREF_2_AE14") (pintype "bidirectional"))
    )
    (net (code "165") (name "/FPGA_CLK_N") (class "Default")
      (node (ref "IC19") (pin "AB30") (pinfunction "IO_L42N_GCLK6_TRDY1_M1LDM_1_AB30") (pintype "bidirectional"))
    )
    (net (code "166") (name "/FPGA_CLK_P") (class "Default")
      (node (ref "IC19") (pin "AB28") (pinfunction "IO_L42P_GCLK7_M1UDM_1_AB28") (pintype "bidirectional"))
    )
    (net (code "167") (name "/FPGPIO1_A2B") (class "Default")
      (node (ref "IC19") (pin "AC28") (pinfunction "IO_L49N_M1DQ11_1_AC28") (pintype "bidirectional"))
    )
    (net (code "168") (name "/FPGPIO2_A2B") (class "Default")
      (node (ref "IC19") (pin "AC27") (pinfunction "IO_L49P_M1DQ10_1_AC27") (pintype "bidirectional"))
    )
    (net (code "169") (name "/FPGPIO34_A2B") (class "Default")
      (node (ref "IC19") (pin "AD30") (pinfunction "IO_L48N_M1DQ9_1_AD30") (pintype "bidirectional"))
    )
    (net (code "170") (name "/FP_GPIO1") (class "Default")
      (node (ref "IC19") (pin "P27") (pinfunction "IO_L32N_A16_M1A9_1_P27") (pintype "bidirectional"))
    )
    (net (code "171") (name "/FP_GPIO2") (class "Default")
      (node (ref "IC19") (pin "R29") (pinfunction "IO_L33P_A15_M1A10_1_R29") (pintype "bidirectional"))
    )
    (net (code "172") (name "/FP_GPIO3") (class "Default")
      (node (ref "IC19") (pin "R30") (pinfunction "IO_L33N_A14_M1A4_1_R30") (pintype "bidirectional"))
    )
    (net (code "173") (name "/FP_GPIO4") (class "Default")
      (node (ref "IC19") (pin "R27") (pinfunction "IO_L34P_A13_M1WE_1_R27") (pintype "bidirectional"))
    )
    (net (code "175") (name "/FP_LEDN0") (class "Default")
      (node (ref "IC19") (pin "M24") (pinfunction "IO_L28N_VREF_1_M24") (pintype "bidirectional"))
    )
    (net (code "176") (name "/FP_LEDN1") (class "Default")
      (node (ref "IC19") (pin "N29") (pinfunction "IO_L29P_A23_M1A13_1_N29") (pintype "bidirectional"))
    )
    (net (code "177") (name "/FP_LEDN2") (class "Default")
      (node (ref "IC19") (pin "N30") (pinfunction "IO_L29N_A22_M1A14_1_N30") (pintype "bidirectional"))
    )
    (net (code "178") (name "/FP_LEDN3") (class "Default")
      (node (ref "IC19") (pin "N27") (pinfunction "IO_L30P_A21_M1RESET_1_N27") (pintype "bidirectional"))
    )
    (net (code "179") (name "/FP_LEDN4") (class "Default")
      (node (ref "IC19") (pin "N28") (pinfunction "IO_L30N_A20_M1A11_1_N28") (pintype "bidirectional"))
    )
    (net (code "180") (name "/FP_LEDN5") (class "Default")
      (node (ref "IC19") (pin "M23") (pinfunction "IO_L28P_1_M23") (pintype "bidirectional"))
    )
    (net (code "181") (name "/FP_LEDN6") (class "Default")
      (node (ref "IC19") (pin "P28") (pinfunction "IO_L31P_A19_M1CKE_1_P28") (pintype "bidirectional"))
    )
    (net (code "182") (name "/FP_LEDN7") (class "Default")
      (node (ref "IC19") (pin "P30") (pinfunction "IO_L31N_A18_M1A12_1_P30") (pintype "bidirectional"))
    )
    (net (code "184") (name "/IO7") (class "Default")
      (node (ref "IC19") (pin "Y25") (pinfunction "IO_L72N_1_Y25") (pintype "bidirectional"))
    )
    (net (code "185") (name "/NOGA0") (class "Default")
      (node (ref "IC19") (pin "Y26") (pinfunction "IO_L47P_FWE_B_M1DQ0_1_Y26") (pintype "bidirectional"))
    )
    (net (code "186") (name "/NOGA1") (class "Default")
      (node (ref "IC19") (pin "AA28") (pinfunction "IO_L46N_FOE_B_M1DQ3_1_AA28") (pintype "bidirectional"))
    )
    (net (code "187") (name "/NOGA2") (class "Default")
      (node (ref "IC19") (pin "AA27") (pinfunction "IO_L46P_FCS_B_M1DQ2_1_AA27") (pintype "bidirectional"))
    )
    (net (code "188") (name "/NOGA3") (class "Default")
      (node (ref "IC19") (pin "AA30") (pinfunction "IO_L45N_A0_M1LDQSN_1_AA30") (pintype "bidirectional"))
    )
    (net (code "189") (name "/NOGA4") (class "Default")
      (node (ref "IC19") (pin "AA29") (pinfunction "IO_L45P_A1_M1LDQS_1_AA29") (pintype "bidirectional"))
    )
    (net (code "190") (name "/OE_SI57X") (class "Default")
      (node (ref "IC19") (pin "T28") (pinfunction "IO_L36P_A9_M1BA0_1_T28") (pintype "bidirectional"))
    )
    (net (code "191") (name "/P2_DATA_N0") (class "Default")
      (node (ref "IC19") (pin "AB19") (pinfunction "IO_L20N_2_AB19") (pintype "bidirectional"))
    )
    (net (code "192") (name "/P2_DATA_N1") (class "Default")
      (node (ref "IC19") (pin "Y20") (pinfunction "IO_L18N_2_Y20") (pintype "bidirectional"))
    )
    (net (code "193") (name "/P2_DATA_N2") (class "Default")
      (node (ref "IC19") (pin "AD19") (pinfunction "IO_L14N_D12_2_AD19") (pintype "bidirectional"))
    )
    (net (code "194") (name "/P2_DATA_N3") (class "Default")
      (node (ref "IC19") (pin "E23") (pinfunction "IO_L60N_0_E23") (pintype "bidirectional"))
    )
    (net (code "195") (name "/P2_DATA_N4") (class "Default")
      (node (ref "IC19") (pin "K21") (pinfunction "IO_L59N_0_K21") (pintype "bidirectional"))
    )
    (net (code "196") (name "/P2_DATA_N5") (class "Default")
      (node (ref "IC19") (pin "A25") (pinfunction "IO_L63N_SCP6_0_A25") (pintype "bidirectional"))
    )
    (net (code "197") (name "/P2_DATA_N6") (class "Default")
      (node (ref "IC19") (pin "G21") (pinfunction "IO_L61N_0_G21") (pintype "bidirectional"))
    )
    (net (code "198") (name "/P2_DATA_N7") (class "Default")
      (node (ref "IC19") (pin "C24") (pinfunction "IO_L64N_SCP4_0_C24") (pintype "bidirectional"))
    )
    (net (code "199") (name "/P2_DATA_N8") (class "Default")
      (node (ref "IC19") (pin "F22") (pinfunction "IO_L58N_0_F22") (pintype "bidirectional"))
    )
    (net (code "200") (name "/P2_DATA_N9") (class "Default")
      (node (ref "IC19") (pin "L20") (pinfunction "IO_L57N_0_L20") (pintype "bidirectional"))
    )
    (net (code "201") (name "/P2_DATA_N10") (class "Default")
      (node (ref "IC19") (pin "Y19") (pinfunction "IO_L22N_2_Y19") (pintype "bidirectional"))
    )
    (net (code "202") (name "/P2_DATA_N11") (class "Default")
      (node (ref "IC19") (pin "AF19") (pinfunction "IO_L19N_2_AF19") (pintype "bidirectional"))
    )
    (net (code "203") (name "/P2_DATA_N12") (class "Default")
      (node (ref "IC19") (pin "D25") (pinfunction "IO_L66N_SCP0_0_D25") (pintype "bidirectional"))
    )
    (net (code "204") (name "/P2_DATA_N13") (class "Default")
      (node (ref "IC19") (pin "AE20") (pinfunction "IO_L17N_2_AE20") (pintype "bidirectional"))
    )
    (net (code "205") (name "/P2_DATA_N14") (class "Default")
      (node (ref "IC19") (pin "E21") (pinfunction "IO_L56N_0_E21") (pintype "bidirectional"))
    )
    (net (code "206") (name "/P2_DATA_N15") (class "Default")
      (node (ref "IC19") (pin "F20") (pinfunction "IO_L54N_0_F20") (pintype "bidirectional"))
    )
    (net (code "207") (name "/P2_DATA_N16") (class "Default")
      (node (ref "IC19") (pin "AE18") (pinfunction "IO_L21N_2_AE18") (pintype "bidirectional"))
    )
    (net (code "208") (name "/P2_DATA_N17") (class "Default")
      (node (ref "IC19") (pin "AF21") (pinfunction "IO_L15N_2_AF21") (pintype "bidirectional"))
    )
    (net (code "209") (name "/P2_DATA_N18") (class "Default")
      (node (ref "IC19") (pin "J20") (pinfunction "IO_L55N_0_J20") (pintype "bidirectional"))
    )
    (net (code "210") (name "/P2_DATA_N19") (class "Default")
      (node (ref "IC19") (pin "H22") (pinfunction "IO_L65N_SCP2_0_H22") (pintype "bidirectional"))
    )
    (net (code "212") (name "/P2_DATA_P0") (class "Default")
      (node (ref "IC19") (pin "AA19") (pinfunction "IO_L20P_2_AA19") (pintype "bidirectional"))
    )
    (net (code "213") (name "/P2_DATA_P1") (class "Default")
      (node (ref "IC19") (pin "W20") (pinfunction "IO_L18P_2_W20") (pintype "bidirectional"))
    )
    (net (code "214") (name "/P2_DATA_P2") (class "Default")
      (node (ref "IC19") (pin "AC19") (pinfunction "IO_L14P_D11_2_AC19") (pintype "bidirectional"))
    )
    (net (code "215") (name "/P2_DATA_P3") (class "Default")
      (node (ref "IC19") (pin "F23") (pinfunction "IO_L60P_0_F23") (pintype "bidirectional"))
    )
    (net (code "216") (name "/P2_DATA_P4") (class "Default")
      (node (ref "IC19") (pin "L21") (pinfunction "IO_L59P_0_L21") (pintype "bidirectional"))
    )
    (net (code "217") (name "/P2_DATA_P5") (class "Default")
      (node (ref "IC19") (pin "B25") (pinfunction "IO_L63P_SCP7_0_B25") (pintype "bidirectional"))
    )
    (net (code "218") (name "/P2_DATA_P6") (class "Default")
      (node (ref "IC19") (pin "H21") (pinfunction "IO_L61P_0_H21") (pintype "bidirectional"))
    )
    (net (code "219") (name "/P2_DATA_P7") (class "Default")
      (node (ref "IC19") (pin "D24") (pinfunction "IO_L64P_SCP5_0_D24") (pintype "bidirectional"))
    )
    (net (code "220") (name "/P2_DATA_P8") (class "Default")
      (node (ref "IC19") (pin "G22") (pinfunction "IO_L58P_0_G22") (pintype "bidirectional"))
    )
    (net (code "221") (name "/P2_DATA_P9") (class "Default")
      (node (ref "IC19") (pin "M20") (pinfunction "IO_L57P_0_M20") (pintype "bidirectional"))
    )
    (net (code "222") (name "/P2_DATA_P10") (class "Default")
      (node (ref "IC19") (pin "W19") (pinfunction "IO_L22P_2_W19") (pintype "bidirectional"))
    )
    (net (code "223") (name "/P2_DATA_P11") (class "Default")
      (node (ref "IC19") (pin "AE19") (pinfunction "IO_L19P_2_AE19") (pintype "bidirectional"))
    )
    (net (code "224") (name "/P2_DATA_P12") (class "Default")
      (node (ref "IC19") (pin "E25") (pinfunction "IO_L66P_SCP1_0_E25") (pintype "bidirectional"))
    )
    (net (code "225") (name "/P2_DATA_P13") (class "Default")
      (node (ref "IC19") (pin "AD20") (pinfunction "IO_L17P_2_AD20") (pintype "bidirectional"))
    )
    (net (code "226") (name "/P2_DATA_P14") (class "Default")
      (node (ref "IC19") (pin "F21") (pinfunction "IO_L56P_0_F21") (pintype "bidirectional"))
    )
    (net (code "227") (name "/P2_DATA_P15") (class "Default")
      (node (ref "IC19") (pin "G20") (pinfunction "IO_L54P_0_G20") (pintype "bidirectional"))
    )
    (net (code "228") (name "/P2_DATA_P16") (class "Default")
      (node (ref "IC19") (pin "AD18") (pinfunction "IO_L21P_2_AD18") (pintype "bidirectional"))
    )
    (net (code "229") (name "/P2_DATA_P17") (class "Default")
      (node (ref "IC19") (pin "AE21") (pinfunction "IO_L15P_2_AE21") (pintype "bidirectional"))
    )
    (net (code "230") (name "/P2_DATA_P18") (class "Default")
      (node (ref "IC19") (pin "K20") (pinfunction "IO_L55P_0_K20") (pintype "bidirectional"))
    )
    (net (code "231") (name "/P2_DATA_P19") (class "Default")
      (node (ref "IC19") (pin "J22") (pinfunction "IO_L65P_SCP3_0_J22") (pintype "bidirectional"))
    )
    (net (code "233") (name "/PLL25DAC1_SYNC_N") (class "Default")
      (node (ref "IC19") (pin "U29") (pinfunction "IO_L37P_A7_M1A0_1_U29") (pintype "bidirectional"))
    )
    (net (code "234") (name "/PLL25DAC2_SYNC_N") (class "Default")
      (node (ref "IC19") (pin "T30") (pinfunction "IO_L36N_A8_M1BA1_1_T30") (pintype "bidirectional"))
    )
    (net (code "235") (name "/PLL25DAC_DIN") (class "Default")
      (node (ref "IC19") (pin "U30") (pinfunction "IO_L37N_A6_M1A1_1_U30") (pintype "bidirectional"))
    )
    (net (code "236") (name "/PLL25DAC_SCLK") (class "Default")
      (node (ref "IC19") (pin "U27") (pinfunction "IO_L38P_A5_M1CLK_1_U27") (pintype "bidirectional"))
    )
    (net (code "237") (name "/PLL_2AFPGA_N") (class "Default")
      (node (ref "IC19") (pin "AA1") (pinfunction "IO_L41N_GCLK26_M3DQ5_3_AA1") (pintype "bidirectional"))
    )
    (net (code "238") (name "/PLL_2AFPGA_P") (class "Default")
      (node (ref "IC19") (pin "AA3") (pinfunction "IO_L41P_GCLK27_M3DQ4_3_AA3") (pintype "bidirectional"))
    )
    (net (code "239") (name "/PUSHBUTTON") (class "Default")
      (node (ref "IC19") (pin "P26") (pinfunction "IO_L32P_A17_M1A8_1_P26") (pintype "bidirectional"))
    )
    (net (code "240") (name "/RSTn") (class "Default")
      (node (ref "IC19") (pin "V28") (pinfunction "IO_L39P_M1A3_1_V28") (pintype "bidirectional"))
    )
    (net (code "241") (name "/RSVD0") (class "Default")
      (node (ref "IC19") (pin "P23") (pinfunction "IO_L56N_1_P23") (pintype "bidirectional"))
    )
    (net (code "242") (name "/RSVD1") (class "Default")
      (node (ref "IC19") (pin "AG29") (pinfunction "IO_L57P_1_AG29") (pintype "bidirectional"))
    )
    (net (code "243") (name "/RSVD2") (class "Default")
      (node (ref "IC19") (pin "AG30") (pinfunction "IO_L57N_1_AG30") (pintype "bidirectional"))
    )
    (net (code "244") (name "/RSVD3") (class "Default")
      (node (ref "IC19") (pin "P24") (pinfunction "IO_L58P_1_P24") (pintype "bidirectional"))
    )
    (net (code "245") (name "/RSVD4") (class "Default")
      (node (ref "IC19") (pin "P25") (pinfunction "IO_L58N_1_P25") (pintype "bidirectional"))
    )
    (net (code "246") (name "/RSVD5") (class "Default")
      (node (ref "IC19") (pin "AH30") (pinfunction "IO_L59P_1_AH30") (pintype "bidirectional"))
    )
    (net (code "247") (name "/RSVD6") (class "Default")
      (node (ref "IC19") (pin "AJ30") (pinfunction "IO_L59N_1_AJ30") (pintype "bidirectional"))
    )
    (net (code "248") (name "/RSVD7") (class "Default")
      (node (ref "IC19") (pin "R24") (pinfunction "IO_L60P_1_R24") (pintype "bidirectional"))
    )
    (net (code "250") (name "/SCL_AFPGA") (class "Default")
      (node (ref "IC19") (pin "Y22") (pinfunction "IO_L70P_1_Y22") (pintype "bidirectional"))
    )
    (net (code "251") (name "/SDA_AFPGA") (class "Default")
      (node (ref "IC19") (pin "Y23") (pinfunction "IO_L70N_1_Y23") (pintype "bidirectional"))
    )
    (net (code "252") (name "/SI57X_CLK_N") (class "Default")
      (node (ref "IC19") (pin "W27") (pinfunction "IO_L41P_GCLK9_IRDY1_M1RASN_1_W27") (pintype "bidirectional"))
    )
    (net (code "253") (name "/SI57X_CLK_P") (class "Default")
      (node (ref "IC19") (pin "W28") (pinfunction "IO_L41N_GCLK8_M1CASN_1_W28") (pintype "bidirectional"))
    )
    (net (code "254") (name "/SI57X_SCL") (class "Default")
      (node (ref "IC19") (pin "R28") (pinfunction "IO_L34N_A12_M1BA2_1_R28") (pintype "bidirectional"))
    )
    (net (code "255") (name "/SI57X_SDA") (class "Default")
      (node (ref "IC19") (pin "T26") (pinfunction "IO_L35P_A11_M1A7_1_T26") (pintype "bidirectional"))
    )
    (net (code "256") (name "/SI57X_TUNE") (class "Default")
      (node (ref "IC19") (pin "T27") (pinfunction "IO_L35N_A10_M1A2_1_T27") (pintype "bidirectional"))
    )
    (net (code "257") (name "/SWITCH0") (class "Default")
      (node (ref "IC19") (pin "Y27") (pinfunction "IO_L47N_LDC_M1DQ1_1_Y27") (pintype "bidirectional"))
    )
    (net (code "258") (name "/SWITCH1") (class "Default")
      (node (ref "IC19") (pin "AD28") (pinfunction "IO_L48P_HDC_M1DQ8_1_AD28") (pintype "bidirectional"))
    )
    (net (code "259") (name "/UART_RXD") (class "Default")
      (node (ref "IC19") (pin "AJ28") (pinfunction "IO_L63P_1_AJ28") (pintype "bidirectional"))
    )
    (net (code "260") (name "/UART_TXD") (class "Default")
      (node (ref "IC19") (pin "AK28") (pinfunction "IO_L63N_1_AK28") (pintype "bidirectional"))
    )
    (net (code "261") (name "/USB_CLKOUT") (class "Default")
      (node (ref "IC19") (pin "AG26") (pinfunction "IO_L73P_1_AG26") (pintype "bidirectional"))
    )
    (net (code "262") (name "/USB_D0") (class "Default")
      (node (ref "IC19") (pin "V23") (pinfunction "IO_L66P_1_V23") (pintype "bidirectional"))
    )
    (net (code "263") (name "/USB_D1") (class "Default")
      (node (ref "IC19") (pin "V24") (pinfunction "IO_L66N_1_V24") (pintype "bidirectional"))
    )
    (net (code "264") (name "/USB_D2") (class "Default")
      (node (ref "IC19") (pin "AD26") (pinfunction "IO_L67P_1_AD26") (pintype "bidirectional"))
    )
    (net (code "265") (name "/USB_D3") (class "Default")
      (node (ref "IC19") (pin "AD27") (pinfunction "IO_L67N_1_AD27") (pintype "bidirectional"))
    )
    (net (code "266") (name "/USB_D4") (class "Default")
      (node (ref "IC19") (pin "W21") (pinfunction "IO_L68P_1_W21") (pintype "bidirectional"))
    )
    (net (code "267") (name "/USB_D5") (class "Default")
      (node (ref "IC19") (pin "W22") (pinfunction "IO_L68N_1_W22") (pintype "bidirectional"))
    )
    (net (code "268") (name "/USB_D6") (class "Default")
      (node (ref "IC19") (pin "AH27") (pinfunction "IO_L69P_1_AH27") (pintype "bidirectional"))
    )
    (net (code "269") (name "/USB_D7") (class "Default")
      (node (ref "IC19") (pin "AK27") (pinfunction "IO_L69N_VREF_1_AK27") (pintype "bidirectional"))
    )
    (net (code "271") (name "/USB_OE#") (class "Default")
      (node (ref "IC19") (pin "AE26") (pinfunction "IO_L71N_1_AE26") (pintype "bidirectional"))
    )
    (net (code "272") (name "/USB_RD#") (class "Default")
      (node (ref "IC19") (pin "Y24") (pinfunction "IO_L72P_1_Y24") (pintype "bidirectional"))
    )
    (net (code "273") (name "/USB_RXF#") (class "Default")
      (node (ref "IC19") (pin "AH26") (pinfunction "IO_L73N_1_AH26") (pintype "bidirectional"))
    )
    (net (code "274") (name "/USB_SIWUA") (class "Default")
      (node (ref "IC19") (pin "AA25") (pinfunction "IO_L74N_DOUT_BUSY_1_AA25") (pintype "bidirectional"))
    )
    (net (code "275") (name "/USB_TXE#") (class "Default")
      (node (ref "IC19") (pin "AA24") (pinfunction "IO_L74P_AWAKE_1_AA24") (pintype "bidirectional"))
    )
    (net (code "276") (name "/USB_WR#") (class "Default")
      (node (ref "IC19") (pin "AE25") (pinfunction "IO_L71P_1_AE25") (pintype "bidirectional"))
    )
    (net (code "277") (name "/USEGA") (class "Default")
      (node (ref "IC19") (pin "Y30") (pinfunction "IO_L44N_A2_M1DQ7_1_Y30") (pintype "bidirectional"))
    )
    (net (code "278") (name "/VME_A1") (class "Default")
      (node (ref "IC19") (pin "AE3") (pinfunction "IO_L30P_3_AE3") (pintype "bidirectional"))
    )
    (net (code "279") (name "/VME_A2") (class "Default")
      (node (ref "IC19") (pin "AE1") (pinfunction "IO_L30N_3_AE1") (pintype "bidirectional"))
    )
    (net (code "280") (name "/VME_A3") (class "Default")
      (node (ref "IC19") (pin "N8") (pinfunction "IO_L31P_3_N8") (pintype "bidirectional"))
    )
    (net (code "281") (name "/VME_A4") (class "Default")
      (node (ref "IC19") (pin "N7") (pinfunction "IO_L31N_VREF_3_N7") (pintype "bidirectional"))
    )
    (net (code "282") (name "/VME_A5") (class "Default")
      (node (ref "IC19") (pin "AC5") (pinfunction "IO_L32P_M3DQ14_3_AC5") (pintype "bidirectional"))
    )
    (net (code "283") (name "/VME_A6") (class "Default")
      (node (ref "IC19") (pin "AC4") (pinfunction "IO_L32N_M3DQ15_3_AC4") (pintype "bidirectional"))
    )
    (net (code "284") (name "/VME_A7") (class "Default")
      (node (ref "IC19") (pin "AD4") (pinfunction "IO_L33P_M3DQ12_3_AD4") (pintype "bidirectional"))
    )
    (net (code "285") (name "/VME_A8") (class "Default")
      (node (ref "IC19") (pin "AD3") (pinfunction "IO_L33N_M3DQ13_3_AD3") (pintype "bidirectional"))
    )
    (net (code "286") (name "/VME_A9") (class "Default")
      (node (ref "IC19") (pin "AB4") (pinfunction "IO_L34P_M3UDQS_3_AB4") (pintype "bidirectional"))
    )
    (net (code "287") (name "/VME_A10") (class "Default")
      (node (ref "IC19") (pin "AB3") (pinfunction "IO_L34N_M3UDQSN_3_AB3") (pintype "bidirectional"))
    )
    (net (code "288") (name "/VME_A11") (class "Default")
      (node (ref "IC19") (pin "AD2") (pinfunction "IO_L35P_M3DQ10_3_AD2") (pintype "bidirectional"))
    )
    (net (code "289") (name "/VME_A12") (class "Default")
      (node (ref "IC19") (pin "AD1") (pinfunction "IO_L35N_M3DQ11_3_AD1") (pintype "bidirectional"))
    )
    (net (code "290") (name "/VME_A13") (class "Default")
      (node (ref "IC19") (pin "AC3") (pinfunction "IO_L36P_M3DQ8_3_AC3") (pintype "bidirectional"))
    )
    (net (code "291") (name "/VME_A14") (class "Default")
      (node (ref "IC19") (pin "AC1") (pinfunction "IO_L36N_M3DQ9_3_AC1") (pintype "bidirectional"))
    )
    (net (code "292") (name "/VME_A15") (class "Default")
      (node (ref "IC19") (pin "Y4") (pinfunction "IO_L37P_M3DQ0_3_Y4") (pintype "bidirectional"))
    )
    (net (code "293") (name "/VME_A16") (class "Default")
      (node (ref "IC19") (pin "Y3") (pinfunction "IO_L37N_M3DQ1_3_Y3") (pintype "bidirectional"))
    )
    (net (code "294") (name "/VME_A17") (class "Default")
      (node (ref "IC19") (pin "Y2") (pinfunction "IO_L38P_M3DQ2_3_Y2") (pintype "bidirectional"))
    )
    (net (code "295") (name "/VME_A18") (class "Default")
      (node (ref "IC19") (pin "Y1") (pinfunction "IO_L38N_M3DQ3_3_Y1") (pintype "bidirectional"))
    )
    (net (code "296") (name "/VME_A19") (class "Default")
      (node (ref "IC19") (pin "AA5") (pinfunction "IO_L39P_M3LDQS_3_AA5") (pintype "bidirectional"))
    )
    (net (code "297") (name "/VME_A20") (class "Default")
      (node (ref "IC19") (pin "AA4") (pinfunction "IO_L39N_M3LDQSN_3_AA4") (pintype "bidirectional"))
    )
    (net (code "298") (name "/VME_A21") (class "Default")
      (node (ref "IC19") (pin "W3") (pinfunction "IO_L40P_M3DQ6_3_W3") (pintype "bidirectional"))
    )
    (net (code "299") (name "/VME_A22") (class "Default")
      (node (ref "IC19") (pin "W1") (pinfunction "IO_L40N_M3DQ7_3_W1") (pintype "bidirectional"))
    )
    (net (code "300") (name "/VME_A23") (class "Default")
      (node (ref "IC19") (pin "V2") (pinfunction "IO_L45P_M3A3_3_V2") (pintype "bidirectional"))
    )
    (net (code "301") (name "/VME_A24") (class "Default")
      (node (ref "IC19") (pin "V1") (pinfunction "IO_L45N_M3ODT_3_V1") (pintype "bidirectional"))
    )
    (net (code "302") (name "/VME_A25") (class "Default")
      (node (ref "IC19") (pin "U5") (pinfunction "IO_L46P_M3CLK_3_U5") (pintype "bidirectional"))
    )
    (net (code "303") (name "/VME_A26") (class "Default")
      (node (ref "IC19") (pin "U4") (pinfunction "IO_L46N_M3CLKN_3_U4") (pintype "bidirectional"))
    )
    (net (code "304") (name "/VME_A27") (class "Default")
      (node (ref "IC19") (pin "U3") (pinfunction "IO_L47P_M3A0_3_U3") (pintype "bidirectional"))
    )
    (net (code "305") (name "/VME_A28") (class "Default")
      (node (ref "IC19") (pin "U1") (pinfunction "IO_L47N_M3A1_3_U1") (pintype "bidirectional"))
    )
    (net (code "306") (name "/VME_A29") (class "Default")
      (node (ref "IC19") (pin "T4") (pinfunction "IO_L48P_M3BA0_3_T4") (pintype "bidirectional"))
    )
    (net (code "307") (name "/VME_A30") (class "Default")
      (node (ref "IC19") (pin "T3") (pinfunction "IO_L48N_M3BA1_3_T3") (pintype "bidirectional"))
    )
    (net (code "308") (name "/VME_A31") (class "Default")
      (node (ref "IC19") (pin "T2") (pinfunction "IO_L49P_M3A7_3_T2") (pintype "bidirectional"))
    )
    (net (code "309") (name "/VME_AM0") (class "Default")
      (node (ref "IC19") (pin "AK2") (pinfunction "IO_L18N_3_AK2") (pintype "bidirectional"))
    )
    (net (code "310") (name "/VME_AM1") (class "Default")
      (node (ref "IC19") (pin "AE4") (pinfunction "IO_L19P_3_AE4") (pintype "bidirectional"))
    )
    (net (code "311") (name "/VME_AM2") (class "Default")
      (node (ref "IC19") (pin "AF4") (pinfunction "IO_L19N_3_AF4") (pintype "bidirectional"))
    )
    (net (code "312") (name "/VME_AM3") (class "Default")
      (node (ref "IC19") (pin "AF3") (pinfunction "IO_L20P_3_AF3") (pintype "bidirectional"))
    )
    (net (code "313") (name "/VME_AM4") (class "Default")
      (node (ref "IC19") (pin "AG3") (pinfunction "IO_L20N_3_AG3") (pintype "bidirectional"))
    )
    (net (code "314") (name "/VME_AM5") (class "Default")
      (node (ref "IC19") (pin "V8") (pinfunction "IO_L21P_3_V8") (pintype "bidirectional"))
    )
    (net (code "316") (name "/VME_AS") (class "Default")
      (node (ref "IC19") (pin "P6") (pinfunction "IO_L56N_3_P6") (pintype "bidirectional"))
    )
    (net (code "318") (name "/VME_A_DIR") (class "Default")
      (node (ref "IC19") (pin "N5") (pinfunction "IO_L53P_M3CKE_3_N5") (pintype "bidirectional"))
    )
    (net (code "319") (name "/VME_A_OEN") (class "Default")
      (node (ref "IC19") (pin "N4") (pinfunction "IO_L53N_M3A12_3_N4") (pintype "bidirectional"))
    )
    (net (code "320") (name "/VME_BERR") (class "Default")
      (node (ref "IC19") (pin "R3") (pinfunction "IO_L51P_M3A10_3_R3") (pintype "bidirectional"))
    )
    (net (code "321") (name "/VME_D0") (class "Default")
      (node (ref "IC19") (pin "AA10") (pinfunction "IO_L1P_3_AA10") (pintype "bidirectional"))
    )
    (net (code "322") (name "/VME_D1") (class "Default")
      (node (ref "IC19") (pin "AA9") (pinfunction "IO_L1N_VREF_3_AA9") (pintype "bidirectional"))
    )
    (net (code "323") (name "/VME_D2") (class "Default")
      (node (ref "IC19") (pin "AD7") (pinfunction "IO_L2P_3_AD7") (pintype "bidirectional"))
    )
    (net (code "324") (name "/VME_D3") (class "Default")
      (node (ref "IC19") (pin "AE7") (pinfunction "IO_L2N_3_AE7") (pintype "bidirectional"))
    )
    (net (code "325") (name "/VME_D4") (class "Default")
      (node (ref "IC19") (pin "Y9") (pinfunction "IO_L3P_3_Y9") (pintype "bidirectional"))
    )
    (net (code "326") (name "/VME_D5") (class "Default")
      (node (ref "IC19") (pin "Y8") (pinfunction "IO_L3N_3_Y8") (pintype "bidirectional"))
    )
    (net (code "327") (name "/VME_D6") (class "Default")
      (node (ref "IC19") (pin "AE6") (pinfunction "IO_L4P_3_AE6") (pintype "bidirectional"))
    )
    (net (code "328") (name "/VME_D7") (class "Default")
      (node (ref "IC19") (pin "AF6") (pinfunction "IO_L4N_3_AF6") (pintype "bidirectional"))
    )
    (net (code "329") (name "/VME_D8") (class "Default")
      (node (ref "IC19") (pin "W11") (pinfunction "IO_L5P_3_W11") (pintype "bidirectional"))
    )
    (net (code "330") (name "/VME_D9") (class "Default")
      (node (ref "IC19") (pin "Y11") (pinfunction "IO_L5N_3_Y11") (pintype "bidirectional"))
    )
    (net (code "331") (name "/VME_D10") (class "Default")
      (node (ref "IC19") (pin "AE5") (pinfunction "IO_L6P_3_AE5") (pintype "bidirectional"))
    )
    (net (code "332") (name "/VME_D11") (class "Default")
      (node (ref "IC19") (pin "AG5") (pinfunction "IO_L6N_3_AG5") (pintype "bidirectional"))
    )
    (net (code "333") (name "/VME_D12") (class "Default")
      (node (ref "IC19") (pin "T7") (pinfunction "IO_L7P_3_T7") (pintype "bidirectional"))
    )
    (net (code "334") (name "/VME_D13") (class "Default")
      (node (ref "IC19") (pin "T6") (pinfunction "IO_L7N_3_T6") (pintype "bidirectional"))
    )
    (net (code "335") (name "/VME_D14") (class "Default")
      (node (ref "IC19") (pin "AA7") (pinfunction "IO_L8P_3_AA7") (pintype "bidirectional"))
    )
    (net (code "336") (name "/VME_D15") (class "Default")
      (node (ref "IC19") (pin "AA6") (pinfunction "IO_L8N_3_AA6") (pintype "bidirectional"))
    )
    (net (code "337") (name "/VME_D16") (class "Default")
      (node (ref "IC19") (pin "AC6") (pinfunction "IO_L9P_3_AC6") (pintype "bidirectional"))
    )
    (net (code "338") (name "/VME_D17") (class "Default")
      (node (ref "IC19") (pin "AD6") (pinfunction "IO_L9N_3_AD6") (pintype "bidirectional"))
    )
    (net (code "339") (name "/VME_D18") (class "Default")
      (node (ref "IC19") (pin "AH5") (pinfunction "IO_L10P_3_AH5") (pintype "bidirectional"))
    )
    (net (code "340") (name "/VME_D19") (class "Default")
      (node (ref "IC19") (pin "AK5") (pinfunction "IO_L10N_3_AK5") (pintype "bidirectional"))
    )
    (net (code "341") (name "/VME_D20") (class "Default")
      (node (ref "IC19") (pin "W10") (pinfunction "IO_L11P_3_W10") (pintype "bidirectional"))
    )
    (net (code "342") (name "/VME_D21") (class "Default")
      (node (ref "IC19") (pin "W9") (pinfunction "IO_L11N_3_W9") (pintype "bidirectional"))
    )
    (net (code "343") (name "/VME_D22") (class "Default")
      (node (ref "IC19") (pin "AB7") (pinfunction "IO_L12P_3_AB7") (pintype "bidirectional"))
    )
    (net (code "344") (name "/VME_D23") (class "Default")
      (node (ref "IC19") (pin "AB6") (pinfunction "IO_L12N_3_AB6") (pintype "bidirectional"))
    )
    (net (code "345") (name "/VME_D24") (class "Default")
      (node (ref "IC19") (pin "W7") (pinfunction "IO_L13P_3_W7") (pintype "bidirectional"))
    )
    (net (code "346") (name "/VME_D25") (class "Default")
      (node (ref "IC19") (pin "W6") (pinfunction "IO_L13N_3_W6") (pintype "bidirectional"))
    )
    (net (code "347") (name "/VME_D26") (class "Default")
      (node (ref "IC19") (pin "AJ4") (pinfunction "IO_L14P_3_AJ4") (pintype "bidirectional"))
    )
    (net (code "348") (name "/VME_D27") (class "Default")
      (node (ref "IC19") (pin "AK4") (pinfunction "IO_L14N_3_AK4") (pintype "bidirectional"))
    )
    (net (code "349") (name "/VME_D28") (class "Default")
      (node (ref "IC19") (pin "T9") (pinfunction "IO_L15P_3_T9") (pintype "bidirectional"))
    )
    (net (code "350") (name "/VME_D29") (class "Default")
      (node (ref "IC19") (pin "T8") (pinfunction "IO_L15N_3_T8") (pintype "bidirectional"))
    )
    (net (code "351") (name "/VME_D30") (class "Default")
      (node (ref "IC19") (pin "AH3") (pinfunction "IO_L16P_3_AH3") (pintype "bidirectional"))
    )
    (net (code "352") (name "/VME_D31") (class "Default")
      (node (ref "IC19") (pin "AK3") (pinfunction "IO_L16N_3_AK3") (pintype "bidirectional"))
    )
    (net (code "353") (name "/VME_DS1") (class "Default")
      (node (ref "IC19") (pin "Y6") (pinfunction "IO_L17N_VREF_3_Y6") (pintype "bidirectional"))
    )
    (net (code "354") (name "/VME_DS2") (class "Default")
      (node (ref "IC19") (pin "Y7") (pinfunction "IO_L17P_3_Y7") (pintype "bidirectional"))
    )
    (net (code "355") (name "/VME_DTACK") (class "Default")
      (node (ref "IC19") (pin "R5") (pinfunction "IO_L50P_M3WE_3_R5") (pintype "bidirectional"))
    )
    (net (code "356") (name "/VME_DTACK_OE") (class "Default")
      (node (ref "IC19") (pin "T1") (pinfunction "IO_L49N_M3A2_3_T1") (pintype "bidirectional"))
    )
    (net (code "358") (name "/VME_D_DIR") (class "Default")
      (node (ref "IC19") (pin "P2") (pinfunction "IO_L54P_M3RESET_3_P2") (pintype "bidirectional"))
    )
    (net (code "359") (name "/VME_D_OEN") (class "Default")
      (node (ref "IC19") (pin "P1") (pinfunction "IO_L54N_M3A11_3_P1") (pintype "bidirectional"))
    )
    (net (code "360") (name "/VME_GA0") (class "Default")
      (node (ref "IC19") (pin "V7") (pinfunction "IO_L21N_3_V7") (pintype "bidirectional"))
    )
    (net (code "361") (name "/VME_GA1") (class "Default")
      (node (ref "IC19") (pin "AH1") (pinfunction "IO_L22P_3_AH1") (pintype "bidirectional"))
    )
    (net (code "362") (name "/VME_GA2") (class "Default")
      (node (ref "IC19") (pin "AJ1") (pinfunction "IO_L22N_3_AJ1") (pintype "bidirectional"))
    )
    (net (code "363") (name "/VME_GA3") (class "Default")
      (node (ref "IC19") (pin "V10") (pinfunction "IO_L23P_3_V10") (pintype "bidirectional"))
    )
    (net (code "364") (name "/VME_GA4") (class "Default")
      (node (ref "IC19") (pin "V9") (pinfunction "IO_L23N_3_V9") (pintype "bidirectional"))
    )
    (net (code "365") (name "/VME_GAP") (class "Default")
      (node (ref "IC19") (pin "M6") (pinfunction "IO_L57N_VREF_3_M6") (pintype "bidirectional"))
    )
    (net (code "367") (name "/VME_IACK") (class "Default")
      (node (ref "IC19") (pin "N1") (pinfunction "IO_L55N_M3A14_3_N1") (pintype "bidirectional"))
    )
    (net (code "368") (name "/VME_IACKIN") (class "Default")
      (node (ref "IC19") (pin "P7") (pinfunction "IO_L56P_3_P7") (pintype "bidirectional"))
    )
    (net (code "369") (name "/VME_IACKOUT") (class "Default")
      (node (ref "IC19") (pin "N3") (pinfunction "IO_L55P_M3A13_3_N3") (pintype "bidirectional"))
    )
    (net (code "370") (name "/VME_IRQ1") (class "Default")
      (node (ref "IC19") (pin "AG4") (pinfunction "IO_L24P_3_AG4") (pintype "bidirectional"))
    )
    (net (code "371") (name "/VME_IRQ2") (class "Default")
      (node (ref "IC19") (pin "AH4") (pinfunction "IO_L24N_3_AH4") (pintype "bidirectional"))
    )
    (net (code "372") (name "/VME_IRQ3") (class "Default")
      (node (ref "IC19") (pin "N10") (pinfunction "IO_L25P_3_N10") (pintype "bidirectional"))
    )
    (net (code "373") (name "/VME_IRQ4") (class "Default")
      (node (ref "IC19") (pin "N9") (pinfunction "IO_L25N_3_N9") (pintype "bidirectional"))
    )
    (net (code "374") (name "/VME_IRQ5") (class "Default")
      (node (ref "IC19") (pin "AF2") (pinfunction "IO_L26P_3_AF2") (pintype "bidirectional"))
    )
    (net (code "375") (name "/VME_IRQ6") (class "Default")
      (node (ref "IC19") (pin "AH2") (pinfunction "IO_L26N_3_AH2") (pintype "bidirectional"))
    )
    (net (code "376") (name "/VME_IRQ7") (class "Default")
      (node (ref "IC19") (pin "R7") (pinfunction "IO_L27P_3_R7") (pintype "bidirectional"))
    )
    (net (code "378") (name "/VME_LWORD") (class "Default")
      (node (ref "IC19") (pin "M7") (pinfunction "IO_L57P_3_M7") (pintype "bidirectional"))
    )
    (net (code "379") (name "/VME_RETRY") (class "Default")
      (node (ref "IC19") (pin "U6") (pinfunction "IO_L29N_3_U6") (pintype "bidirectional"))
    )
    (net (code "380") (name "/VME_RETRY_OE") (class "Default")
      (node (ref "IC19") (pin "R4") (pinfunction "IO_L50N_M3BA2_3_R4") (pintype "bidirectional"))
    )
    (net (code "381") (name "/VME_SYSCLK") (class "Default")
      (node (ref "IC19") (pin "P3") (pinfunction "IO_L52N_M3A9_3_P3") (pintype "bidirectional"))
    )
    (net (code "382") (name "/VME_SYSRESET") (class "Default")
      (node (ref "IC19") (pin "P4") (pinfunction "IO_L52P_M3A8_3_P4") (pintype "bidirectional"))
    )
    (net (code "383") (name "/VME_WRITE") (class "Default")
      (node (ref "IC19") (pin "R1") (pinfunction "IO_L51N_M3A4_3_R1") (pintype "bidirectional"))
    )
    (net (code "384") (name "/WR_LOS") (class "Default")
      (node (ref "IC19") (pin "AE27") (pinfunction "IO_L52P_M1DQ14_1_AE27") (pintype "bidirectional"))
    )
    (net (code "385") (name "/WR_MODDEF0") (class "Default")
      (node (ref "IC19") (pin "W24") (pinfunction "IO_L53P_1_W24") (pintype "bidirectional"))
    )
    (net (code "386") (name "/WR_MODDEF1") (class "Default")
      (node (ref "IC19") (pin "W29") (pinfunction "IO_L43P_GCLK5_M1DQ4_1_W29") (pintype "bidirectional"))
    )
    (net (code "387") (name "/WR_MODDEF2") (class "Default")
      (node (ref "IC19") (pin "AE28") (pinfunction "IO_L52N_M1DQ15_1_AE28") (pintype "bidirectional"))
    )
    (net (code "388") (name "/WR_RATESELECT") (class "Default")
      (node (ref "IC19") (pin "W30") (pinfunction "IO_L43N_GCLK4_M1DQ5_1_W30") (pintype "bidirectional"))
    )
    (net (code "389") (name "/WR_TXDISABLE") (class "Default")
      (node (ref "IC19") (pin "W25") (pinfunction "IO_L53N_VREF_1_W25") (pintype "bidirectional"))
    )
    (net (code "390") (name "/WR_TXFAULT") (class "Default")
      (node (ref "IC19") (pin "R21") (pinfunction "IO_L54P_1_R21") (pintype "bidirectional"))
    )
    (net (code "391") (name "GND") (class "Default")
      (node (ref "C18") (pin "1") (pinfunction "1_1") (pintype "passive"))
      (node (ref "C369") (pin "1") (pinfunction "1_1") (pintype "passive"))
      (node (ref "C370") (pin "1") (pinfunction "1_1") (pintype "passive"))
      (node (ref "C371") (pin "1") (pinfunction "1_1") (pintype "passive"))
      (node (ref "C372") (pin "1") (pinfunction "1_1") (pintype "passive"))
      (node (ref "C373") (pin "1") (pinfunction "1_1") (pintype "passive"))
      (node (ref "C378") (pin "2") (pinfunction "2_2") (pintype "passive"))
      (node (ref "C387") (pin "1") (pinfunction "1_1") (pintype "passive"))
      (node (ref "C390") (pin "1") (pinfunction "1_1") (pintype "passive"))
      (node (ref "LD10") (pin "1") (pinfunction "C_1") (pintype "passive"))
      (node (ref "LD5") (pin "1") (pinfunction "C_1") (pintype "passive"))
      (node (ref "LD8") (pin "1") (pinfunction "C_1") (pintype "passive"))
      (node (ref "LD9") (pin "1") (pinfunction "C_1") (pintype "passive"))
      (node (ref "R17") (pin "1") (pinfunction "1_1") (pintype "passive"))
    )
    (net (code "392") (name "Net-(IC19A-IO_L1P_HSWAPEN_0)") (class "Default")
      (node (ref "IC19") (pin "H9") (pinfunction "IO_L1P_HSWAPEN_0_H9") (pintype "bidirectional"))
      (node (ref "R14") (pin "1") (pinfunction "1_1") (pintype "passive"))
      (node (ref "R17") (pin "2") (pinfunction "2_2") (pintype "passive"))
    )
    (net (code "393") (name "Net-(IC19D-CMPCS_B_2)") (class "Default")
      (node (ref "IC19") (pin "AC25") (pinfunction "CMPCS_B_2_AC25") (pintype "bidirectional"))
      (node (ref "R21") (pin "2") (pinfunction "2_2") (pintype "passive"))
    )
    (net (code "394") (name "Net-(LD5-A)") (class "Default")
      (node (ref "LD5") (pin "2") (pinfunction "A_2") (pintype "passive"))
      (node (ref "R126") (pin "2") (pinfunction "2_2") (pintype "passive"))
    )
    (net (code "395") (name "Net-(LD8-A)") (class "Default")
      (node (ref "LD8") (pin "2") (pinfunction "A_2") (pintype "passive"))
      (node (ref "R2") (pin "2") (pinfunction "2_2") (pintype "passive"))
    )
    (net (code "396") (name "Net-(LD9-A)") (class "Default")
      (node (ref "LD9") (pin "2") (pinfunction "A_2") (pintype "passive"))
      (node (ref "R3") (pin "2") (pinfunction "2_2") (pintype "passive"))
    )
    (net (code "397") (name "Net-(LD10-A)") (class "Default")
      (node (ref "LD10") (pin "2") (pinfunction "A_2") (pintype "passive"))
      (node (ref "R7") (pin "2") (pinfunction "2_2") (pintype "passive"))
    )
    (net (code "398") (name "P2V5") (class "Default")
      (node (ref "R14") (pin "2") (pinfunction "2_2") (pintype "passive"))
      (node (ref "R21") (pin "1") (pinfunction "1_1") (pintype "passive"))
    )
    (net (code "399") (name "unconnected-(IC19A-IO_L8P_0-PadB6)") (class "Default")
      (node (ref "IC19") (pin "B6") (pinfunction "IO_L8P_0_B6") (pintype "bidirectional"))
    )
    (net (code "400") (name "unconnected-(IC19A-IO_L21N_0-PadL13)") (class "Default")
      (node (ref "IC19") (pin "L13") (pinfunction "IO_L21N_0_L13") (pintype "bidirectional"))
    )
    (net (code "401") (name "unconnected-(IC19A-IO_L21P_0-PadM13)") (class "Default")
      (node (ref "IC19") (pin "M13") (pinfunction "IO_L21P_0_M13") (pintype "bidirectional"))
    )
    (net (code "402") (name "unconnected-(IC19A-IO_L22N_0-PadF12)") (class "Default")
      (node (ref "IC19") (pin "F12") (pinfunction "IO_L22N_0_F12") (pintype "bidirectional"))
    )
    (net (code "403") (name "unconnected-(IC19A-IO_L22P_0-PadG12)") (class "Default")
      (node (ref "IC19") (pin "G12") (pinfunction "IO_L22P_0_G12") (pintype "bidirectional"))
    )
    (net (code "404") (name "unconnected-(IC19A-IO_L23N_0-PadK14)") (class "Default")
      (node (ref "IC19") (pin "K14") (pinfunction "IO_L23N_0_K14") (pintype "bidirectional"))
    )
    (net (code "405") (name "unconnected-(IC19A-IO_L23P_0-PadL14)") (class "Default")
      (node (ref "IC19") (pin "L14") (pinfunction "IO_L23P_0_L14") (pintype "bidirectional"))
    )
    (net (code "406") (name "unconnected-(IC19B-IO_L35N_GCLK16_0-PadA15)") (class "Default")
      (node (ref "IC19") (pin "A15") (pinfunction "IO_L35N_GCLK16_0_A15") (pintype "bidirectional"))
    )
    (net (code "407") (name "unconnected-(IC19B-IO_L35P_GCLK17_0-PadB15)") (class "Default")
      (node (ref "IC19") (pin "B15") (pinfunction "IO_L35P_GCLK17_0_B15") (pintype "bidirectional"))
    )
    (net (code "408") (name "unconnected-(IC19B-IO_L36N_GCLK14_0-PadA16)") (class "Default")
      (node (ref "IC19") (pin "A16") (pinfunction "IO_L36N_GCLK14_0_A16") (pintype "bidirectional"))
    )
    (net (code "409") (name "unconnected-(IC19B-IO_L36P_GCLK15_0-PadC16)") (class "Default")
      (node (ref "IC19") (pin "C16") (pinfunction "IO_L36P_GCLK15_0_C16") (pintype "bidirectional+no_connect"))
    )
    (net (code "410") (name "unconnected-(IC19B-IO_L38P_0-PadB17)") (class "Default")
      (node (ref "IC19") (pin "B17") (pinfunction "IO_L38P_0_B17") (pintype "bidirectional"))
    )
    (net (code "411") (name "unconnected-(IC19B-IO_L62P_0-PadF24)") (class "Default")
      (node (ref "IC19") (pin "F24") (pinfunction "IO_L62P_0_F24") (pintype "bidirectional"))
    )
    (net (code "412") (name "unconnected-(IC19C-IO_L38N_A4_M1CLKN_1-PadU28)") (class "Default")
      (node (ref "IC19") (pin "U28") (pinfunction "IO_L38N_A4_M1CLKN_1_U28") (pintype "bidirectional"))
    )
    (net (code "413") (name "unconnected-(IC19C-IO_L39N_M1ODT_1-PadV30)") (class "Default")
      (node (ref "IC19") (pin "V30") (pinfunction "IO_L39N_M1ODT_1_V30") (pintype "bidirectional"))
    )
    (net (code "414") (name "unconnected-(IC19C-IO_L40N_GCLK10_M1A6_1-PadV27)") (class "Default")
      (node (ref "IC19") (pin "V27") (pinfunction "IO_L40N_GCLK10_M1A6_1_V27") (pintype "bidirectional"))
    )
    (net (code "415") (name "unconnected-(IC19C-IO_L44P_A3_M1DQ6_1-PadY28)") (class "Default")
      (node (ref "IC19") (pin "Y28") (pinfunction "IO_L44P_A3_M1DQ6_1_Y28") (pintype "bidirectional"))
    )
    (net (code "416") (name "unconnected-(IC19C-IO_L50N_M1UDQSN_1-PadAC30)") (class "Default")
      (node (ref "IC19") (pin "AC30") (pinfunction "IO_L50N_M1UDQSN_1_AC30") (pintype "bidirectional"))
    )
    (net (code "417") (name "unconnected-(IC19C-IO_L50P_M1UDQS_1-PadAC29)") (class "Default")
      (node (ref "IC19") (pin "AC29") (pinfunction "IO_L50P_M1UDQS_1_AC29") (pintype "bidirectional"))
    )
    (net (code "418") (name "unconnected-(IC19C-IO_L51N_M1DQ13_1-PadAE30)") (class "Default")
      (node (ref "IC19") (pin "AE30") (pinfunction "IO_L51N_M1DQ13_1_AE30") (pintype "bidirectional"))
    )
    (net (code "419") (name "unconnected-(IC19C-IO_L51P_M1DQ12_1-PadAE29)") (class "Default")
      (node (ref "IC19") (pin "AE29") (pinfunction "IO_L51P_M1DQ12_1_AE29") (pintype "bidirectional"))
    )
    (net (code "420") (name "unconnected-(IC19C-IO_L54N_1-PadR22)") (class "Default")
      (node (ref "IC19") (pin "R22") (pinfunction "IO_L54N_1_R22") (pintype "bidirectional"))
    )
    (net (code "421") (name "unconnected-(IC19C-IO_L55N_1-PadAF30)") (class "Default")
      (node (ref "IC19") (pin "AF30") (pinfunction "IO_L55N_1_AF30") (pintype "bidirectional"))
    )
    (net (code "422") (name "unconnected-(IC19C-IO_L55P_1-PadAF28)") (class "Default")
      (node (ref "IC19") (pin "AF28") (pinfunction "IO_L55P_1_AF28") (pintype "bidirectional"))
    )
    (net (code "423") (name "unconnected-(IC19C-IO_L56P_1-PadP22)") (class "Default")
      (node (ref "IC19") (pin "P22") (pinfunction "IO_L56P_1_P22") (pintype "bidirectional"))
    )
    (net (code "424") (name "unconnected-(IC19C-IO_L60N_1-PadR25)") (class "Default")
      (node (ref "IC19") (pin "R25") (pinfunction "IO_L60N_1_R25") (pintype "bidirectional"))
    )
    (net (code "425") (name "unconnected-(IC19C-IO_L64N_1-PadU25)") (class "Default")
      (node (ref "IC19") (pin "U25") (pinfunction "IO_L64N_1_U25") (pintype "bidirectional"))
    )
    (net (code "426") (name "unconnected-(IC19C-IO_L64P_1-PadU24)") (class "Default")
      (node (ref "IC19") (pin "U24") (pinfunction "IO_L64P_1_U24") (pintype "bidirectional"))
    )
    (net (code "427") (name "unconnected-(IC19C-IO_L65N_1-PadAG28)") (class "Default")
      (node (ref "IC19") (pin "AG28") (pinfunction "IO_L65N_1_AG28") (pintype "bidirectional"))
    )
    (net (code "428") (name "unconnected-(IC19C-IO_L65P_1-PadAG27)") (class "Default")
      (node (ref "IC19") (pin "AG27") (pinfunction "IO_L65P_1_AG27") (pintype "bidirectional"))
    )
    (net (code "429") (name "unconnected-(IC19D-IO_L4P_2-PadAB23)") (class "Default")
      (node (ref "IC19") (pin "AB23") (pinfunction "IO_L4P_2_AB23") (pintype "bidirectional"))
    )
    (net (code "430") (name "unconnected-(IC19D-IO_L13N_D10_2-PadAH24)") (class "Default")
      (node (ref "IC19") (pin "AH24") (pinfunction "IO_L13N_D10_2_AH24") (pintype "bidirectional"))
    )
    (net (code "431") (name "unconnected-(IC19D-IO_L16P_2-PadAA18)") (class "Default")
      (node (ref "IC19") (pin "AA18") (pinfunction "IO_L16P_2_AA18") (pintype "bidirectional"))
    )
    (net (code "432") (name "unconnected-(IC19D-IO_L23N_2-PadAD17)") (class "Default")
      (node (ref "IC19") (pin "AD17") (pinfunction "IO_L23N_2_AD17") (pintype "bidirectional"))
    )
    (net (code "433") (name "unconnected-(IC19D-IO_L23P_2-PadAB17)") (class "Default")
      (node (ref "IC19") (pin "AB17") (pinfunction "IO_L23P_2_AB17") (pintype "bidirectional"))
    )
    (net (code "434") (name "unconnected-(IC19D-IO_L28N_2-PadAF17)") (class "Default")
      (node (ref "IC19") (pin "AF17") (pinfunction "IO_L28N_2_AF17") (pintype "bidirectional"))
    )
    (net (code "435") (name "unconnected-(IC19D-IO_L28P_2-PadAE17)") (class "Default")
      (node (ref "IC19") (pin "AE17") (pinfunction "IO_L28P_2_AE17") (pintype "bidirectional"))
    )
    (net (code "436") (name "unconnected-(IC19D-IO_L29N_GCLK2_2-PadAD16)") (class "Default")
      (node (ref "IC19") (pin "AD16") (pinfunction "IO_L29N_GCLK2_2_AD16") (pintype "bidirectional"))
    )
    (net (code "437") (name "unconnected-(IC19D-IO_L29P_GCLK3_2-PadAC16)") (class "Default")
      (node (ref "IC19") (pin "AC16") (pinfunction "IO_L29P_GCLK3_2_AC16") (pintype "bidirectional"))
    )
    (net (code "438") (name "unconnected-(IC19D-IO_L32N_GCLK28_2-PadAK17)") (class "Default")
      (node (ref "IC19") (pin "AK17") (pinfunction "IO_L32N_GCLK28_2_AK17") (pintype "bidirectional"))
    )
    (net (code "439") (name "unconnected-(IC19D-IO_L32P_GCLK29_2-PadAJ17)") (class "Default")
      (node (ref "IC19") (pin "AJ17") (pinfunction "IO_L32P_GCLK29_2_AJ17") (pintype "bidirectional"))
    )
    (net (code "440") (name "unconnected-(IC19E-IO_L40N_2-PadAC14)") (class "Default")
      (node (ref "IC19") (pin "AC14") (pinfunction "IO_L40N_2_AC14") (pintype "bidirectional"))
    )
    (net (code "441") (name "unconnected-(IC19E-IO_L40P_2-PadAB14)") (class "Default")
      (node (ref "IC19") (pin "AB14") (pinfunction "IO_L40P_2_AB14") (pintype "bidirectional"))
    )
    (net (code "442") (name "unconnected-(IC19E-IO_L41P_2-PadAD14)") (class "Default")
      (node (ref "IC19") (pin "AD14") (pinfunction "IO_L41P_2_AD14") (pintype "bidirectional"))
    )
    (net (code "443") (name "unconnected-(IC19E-IO_L47N_2-PadAF13)") (class "Default")
      (node (ref "IC19") (pin "AF13") (pinfunction "IO_L47N_2_AF13") (pintype "bidirectional"))
    )
    (net (code "444") (name "unconnected-(IC19E-IO_L47P_2-PadAE13)") (class "Default")
      (node (ref "IC19") (pin "AE13") (pinfunction "IO_L47P_2_AE13") (pintype "bidirectional"))
    )
    (net (code "445") (name "unconnected-(IC19E-IO_L48P_D7_2-PadAB13)") (class "Default")
      (node (ref "IC19") (pin "AB13") (pinfunction "IO_L48P_D7_2_AB13") (pintype "bidirectional"))
    )
    (net (code "446") (name "unconnected-(IC19E-IO_L61P_2-PadAC9)") (class "Default")
      (node (ref "IC19") (pin "AC9") (pinfunction "IO_L61P_2_AC9") (pintype "bidirectional"))
    )
    (net (code "447") (name "unconnected-(IC19E-IO_L64N_D9_2-PadAH6)") (class "Default")
      (node (ref "IC19") (pin "AH6") (pinfunction "IO_L64N_D9_2_AH6") (pintype "bidirectional"))
    )
    (net (code "448") (name "unconnected-(IC19E-IO_L64P_D8_2-PadAG6)") (class "Default")
      (node (ref "IC19") (pin "AG6") (pinfunction "IO_L64P_D8_2_AG6") (pintype "bidirectional"))
    )
    (net (code "449") (name "unconnected-(IC19F-IO_L18P_3-PadAJ2)") (class "Default")
      (node (ref "IC19") (pin "AJ2") (pinfunction "IO_L18P_3_AJ2") (pintype "bidirectional"))
    )
    (net (code "450") (name "unconnected-(IC19F-IO_L27N_3-PadR6)") (class "Default")
      (node (ref "IC19") (pin "R6") (pinfunction "IO_L27N_3_R6") (pintype "bidirectional"))
    )
    (net (code "451") (name "unconnected-(IC19F-IO_L28N_3-PadAG1)") (class "Default")
      (node (ref "IC19") (pin "AG1") (pinfunction "IO_L28N_3_AG1") (pintype "bidirectional"))
    )
    (net (code "452") (name "unconnected-(IC19F-IO_L28P_3-PadAF1)") (class "Default")
      (node (ref "IC19") (pin "AF1") (pinfunction "IO_L28P_3_AF1") (pintype "bidirectional"))
    )
    (net (code "453") (name "unconnected-(IC19F-IO_L29P_3-PadU7)") (class "Default")
      (node (ref "IC19") (pin "U7") (pinfunction "IO_L29P_3_U7") (pintype "bidirectional"))
    )
    (net (code "454") (name "unconnected-(IC19G-IO_L42N_GCLK24_M3LDM_3-PadAB1)") (class "Default")
      (node (ref "IC19") (pin "AB1") (pinfunction "IO_L42N_GCLK24_M3LDM_3_AB1") (pintype "bidirectional"))
    )
    (net (code "455") (name "unconnected-(IC19G-IO_L42P_GCLK25_TRDY2_M3UDM_3-PadAB2)") (class "Default")
      (node (ref "IC19") (pin "AB2") (pinfunction "IO_L42P_GCLK25_TRDY2_M3UDM_3_AB2") (pintype "bidirectional"))
    )
    (net (code "456") (name "unconnected-(IC19G-IO_L43N_GCLK22_IRDY2_M3CASN_3-PadW4)") (class "Default")
      (node (ref "IC19") (pin "W4") (pinfunction "IO_L43N_GCLK22_IRDY2_M3CASN_3_W4") (pintype "bidirectional"))
    )
    (net (code "457") (name "unconnected-(IC19G-IO_L43P_GCLK23_M3RASN_3-PadW5)") (class "Default")
      (node (ref "IC19") (pin "W5") (pinfunction "IO_L43P_GCLK23_M3RASN_3_W5") (pintype "bidirectional"))
    )
    (net (code "458") (name "unconnected-(IC19G-IO_L44N_GCLK20_M3A6_3-PadV3)") (class "Default")
      (node (ref "IC19") (pin "V3") (pinfunction "IO_L44N_GCLK20_M3A6_3_V3") (pintype "bidirectional"))
    )
    (net (code "459") (name "unconnected-(IC19G-IO_L44P_GCLK21_M3A5_3-PadV4)") (class "Default")
      (node (ref "IC19") (pin "V4") (pinfunction "IO_L44P_GCLK21_M3A5_3_V4") (pintype "bidirectional"))
    )
  )
)
